# M8330.net
KiCad netlist of a schematic drawn in EAGLE
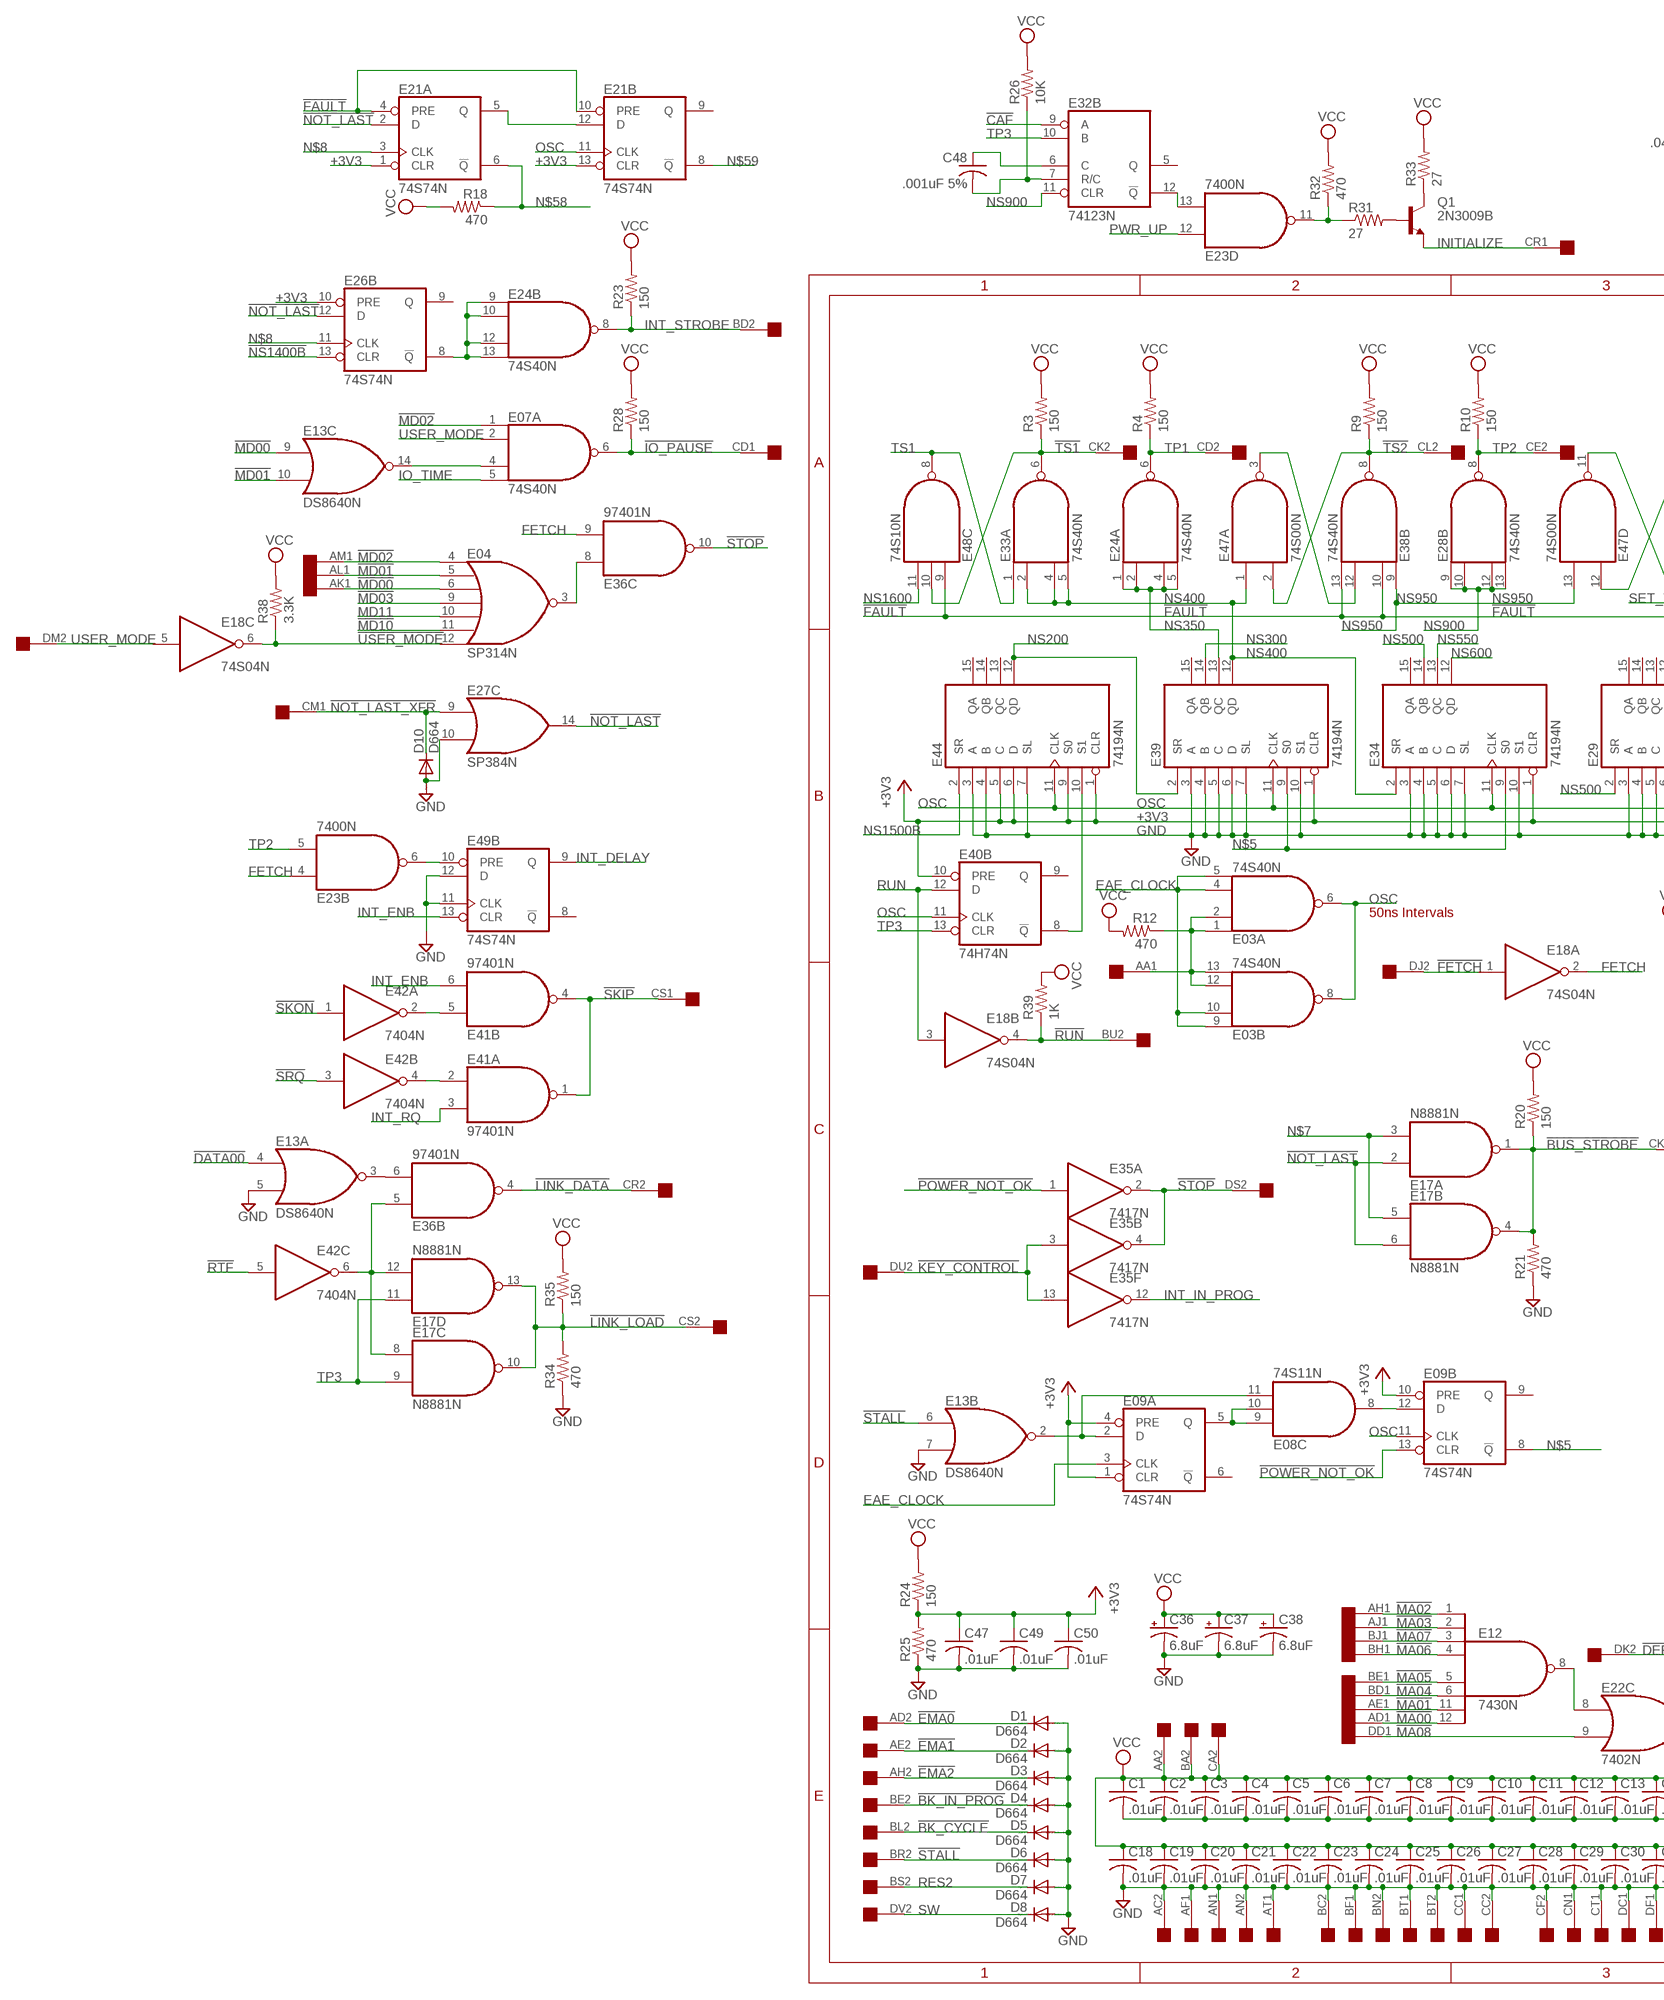
[diagram p0: schematic, sheet 1, part 1 of 2]
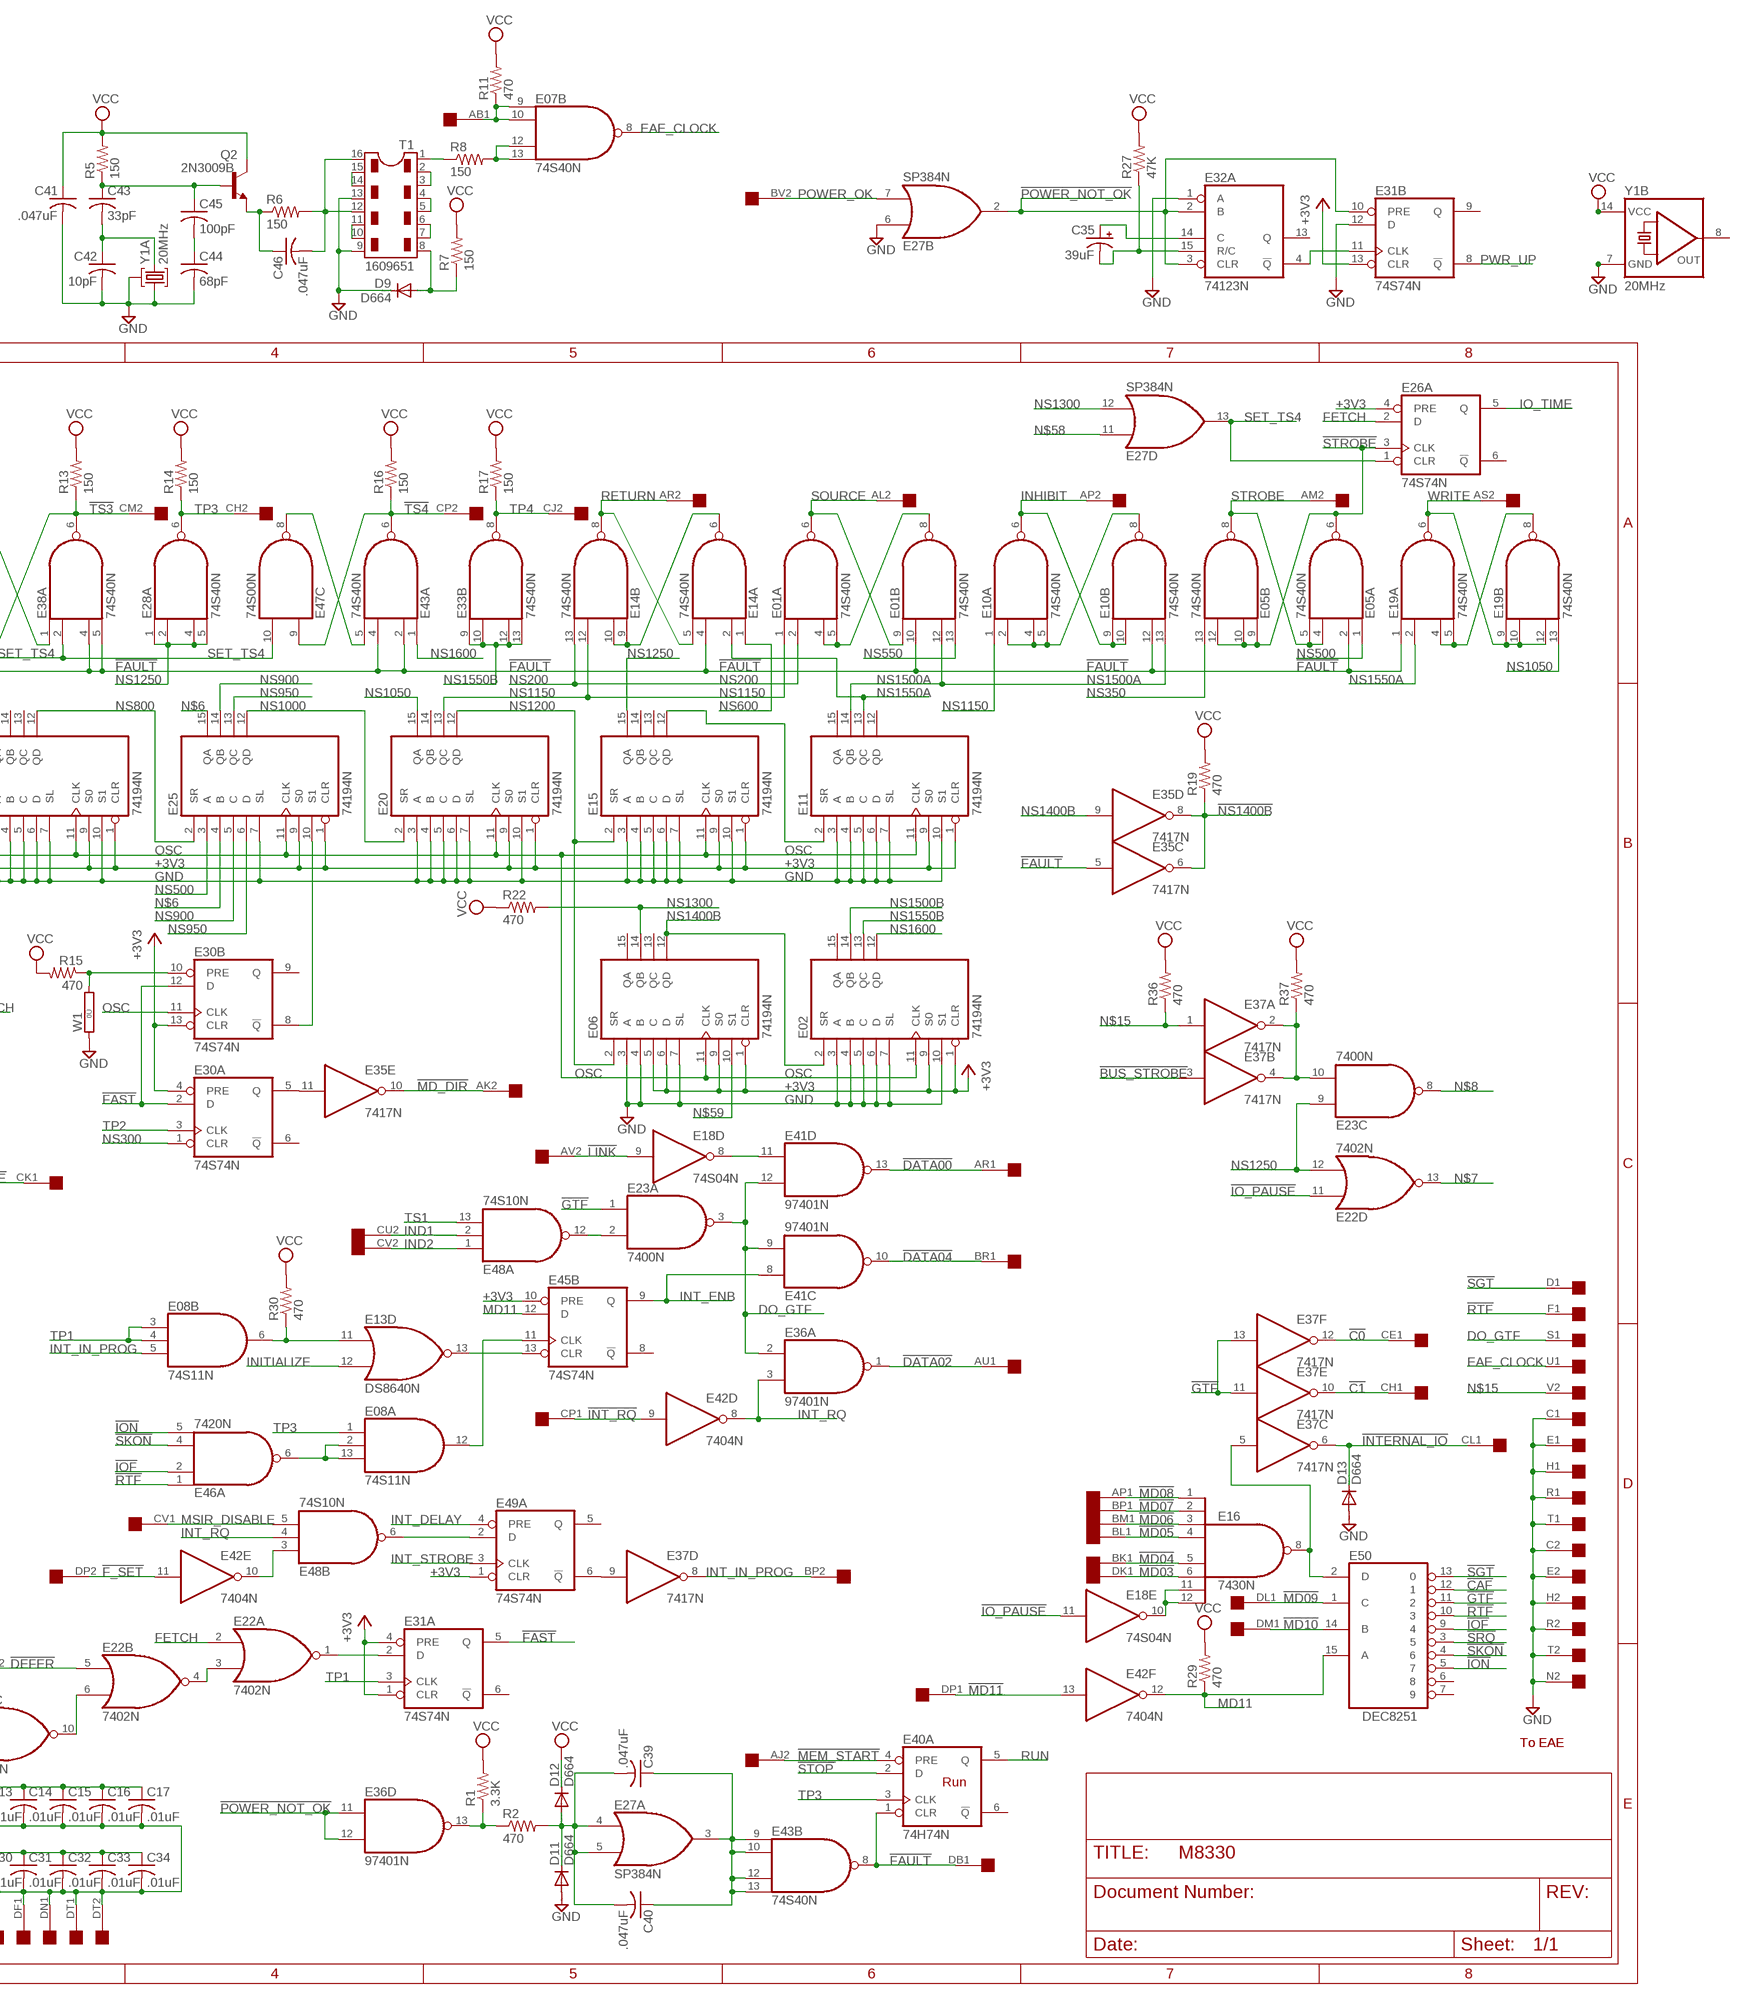
[diagram p1: schematic, sheet 1, part 2 of 2]

(export (version "E")
  (design (tool "Eeschema 10.0.6"))
  (components
    (comp (ref "C1")
      (value ".01uF")
      (footprint "eagle-import:C050-025X075")
      (libsource (lib "eagle-import") (part "C-US050-025X075"))
    )
    (comp (ref "C2")
      (value ".01uF")
      (footprint "eagle-import:C050-025X075")
      (libsource (lib "eagle-import") (part "C-US050-025X075"))
    )
    (comp (ref "C3")
      (value ".01uF")
      (footprint "eagle-import:C050-025X075")
      (libsource (lib "eagle-import") (part "C-US050-025X075"))
    )
    (comp (ref "C4")
      (value ".01uF")
      (footprint "eagle-import:C050-025X075")
      (libsource (lib "eagle-import") (part "C-US050-025X075"))
    )
    (comp (ref "C5")
      (value ".01uF")
      (footprint "eagle-import:C050-025X075")
      (libsource (lib "eagle-import") (part "C-US050-025X075"))
    )
    (comp (ref "C6")
      (value ".01uF")
      (footprint "eagle-import:C050-025X075")
      (libsource (lib "eagle-import") (part "C-US050-025X075"))
    )
    (comp (ref "C7")
      (value ".01uF")
      (footprint "eagle-import:C050-025X075")
      (libsource (lib "eagle-import") (part "C-US050-025X075"))
    )
    (comp (ref "C8")
      (value ".01uF")
      (footprint "eagle-import:C050-025X075")
      (libsource (lib "eagle-import") (part "C-US050-025X075"))
    )
    (comp (ref "C9")
      (value ".01uF")
      (footprint "eagle-import:C050-025X075")
      (libsource (lib "eagle-import") (part "C-US050-025X075"))
    )
    (comp (ref "C10")
      (value ".01uF")
      (footprint "eagle-import:C050-025X075")
      (libsource (lib "eagle-import") (part "C-US050-025X075"))
    )
    (comp (ref "C11")
      (value ".01uF")
      (footprint "eagle-import:C050-025X075")
      (libsource (lib "eagle-import") (part "C-US050-025X075"))
    )
    (comp (ref "C12")
      (value ".01uF")
      (footprint "eagle-import:C050-025X075")
      (libsource (lib "eagle-import") (part "C-US050-025X075"))
    )
    (comp (ref "C13")
      (value ".01uF")
      (footprint "eagle-import:C050-025X075")
      (libsource (lib "eagle-import") (part "C-US050-025X075"))
    )
    (comp (ref "C14")
      (value ".01uF")
      (footprint "eagle-import:C050-025X075")
      (libsource (lib "eagle-import") (part "C-US050-025X075"))
    )
    (comp (ref "C15")
      (value ".01uF")
      (footprint "eagle-import:C050-025X075")
      (libsource (lib "eagle-import") (part "C-US050-025X075"))
    )
    (comp (ref "C16")
      (value ".01uF")
      (footprint "eagle-import:C050-025X075")
      (libsource (lib "eagle-import") (part "C-US050-025X075"))
    )
    (comp (ref "C17")
      (value ".01uF")
      (footprint "eagle-import:C050-025X075")
      (libsource (lib "eagle-import") (part "C-US050-025X075"))
    )
    (comp (ref "C18")
      (value ".01uF")
      (footprint "eagle-import:C050-025X075")
      (libsource (lib "eagle-import") (part "C-US050-025X075"))
    )
    (comp (ref "C19")
      (value ".01uF")
      (footprint "eagle-import:C050-025X075")
      (libsource (lib "eagle-import") (part "C-US050-025X075"))
    )
    (comp (ref "C20")
      (value ".01uF")
      (footprint "eagle-import:C050-025X075")
      (libsource (lib "eagle-import") (part "C-US050-025X075"))
    )
    (comp (ref "C21")
      (value ".01uF")
      (footprint "eagle-import:C050-025X075")
      (libsource (lib "eagle-import") (part "C-US050-025X075"))
    )
    (comp (ref "C22")
      (value ".01uF")
      (footprint "eagle-import:C050-025X075")
      (libsource (lib "eagle-import") (part "C-US050-025X075"))
    )
    (comp (ref "C23")
      (value ".01uF")
      (footprint "eagle-import:C050-025X075")
      (libsource (lib "eagle-import") (part "C-US050-025X075"))
    )
    (comp (ref "C24")
      (value ".01uF")
      (footprint "eagle-import:C050-025X075")
      (libsource (lib "eagle-import") (part "C-US050-025X075"))
    )
    (comp (ref "C25")
      (value ".01uF")
      (footprint "eagle-import:C050-025X075")
      (libsource (lib "eagle-import") (part "C-US050-025X075"))
    )
    (comp (ref "C26")
      (value ".01uF")
      (footprint "eagle-import:C050-025X075")
      (libsource (lib "eagle-import") (part "C-US050-025X075"))
    )
    (comp (ref "C27")
      (value ".01uF")
      (footprint "eagle-import:C050-025X075")
      (libsource (lib "eagle-import") (part "C-US050-025X075"))
    )
    (comp (ref "C28")
      (value ".01uF")
      (footprint "eagle-import:C050-025X075")
      (libsource (lib "eagle-import") (part "C-US050-025X075"))
    )
    (comp (ref "C29")
      (value ".01uF")
      (footprint "eagle-import:C050-025X075")
      (libsource (lib "eagle-import") (part "C-US050-025X075"))
    )
    (comp (ref "C30")
      (value ".01uF")
      (footprint "eagle-import:C050-025X075")
      (libsource (lib "eagle-import") (part "C-US050-025X075"))
    )
    (comp (ref "C31")
      (value ".01uF")
      (footprint "eagle-import:C050-025X075")
      (libsource (lib "eagle-import") (part "C-US050-025X075"))
    )
    (comp (ref "C32")
      (value ".01uF")
      (footprint "eagle-import:C050-025X075")
      (libsource (lib "eagle-import") (part "C-US050-025X075"))
    )
    (comp (ref "C33")
      (value ".01uF")
      (footprint "eagle-import:C050-025X075")
      (libsource (lib "eagle-import") (part "C-US050-025X075"))
    )
    (comp (ref "C34")
      (value ".01uF")
      (footprint "eagle-import:C050-025X075")
      (libsource (lib "eagle-import") (part "C-US050-025X075"))
    )
    (comp (ref "C35")
      (value "39uF")
      (footprint "eagle-import:E12-8")
      (libsource (lib "eagle-import") (part "CPOL-USE20-8AXIAL"))
    )
    (comp (ref "C36")
      (value "6.8uF")
      (footprint "eagle-import:E12-8")
      (libsource (lib "eagle-import") (part "CPOL-USE20-8AXIAL"))
    )
    (comp (ref "C37")
      (value "6.8uF")
      (footprint "eagle-import:E12-8")
      (libsource (lib "eagle-import") (part "CPOL-USE20-8AXIAL"))
    )
    (comp (ref "C38")
      (value "6.8uF")
      (footprint "eagle-import:E12-8")
      (libsource (lib "eagle-import") (part "CPOL-USE20-8AXIAL"))
    )
    (comp (ref "C39")
      (value ".047uF")
      (footprint "eagle-import:C050-025X075")
      (libsource (lib "eagle-import") (part "C-US050-025X075"))
    )
    (comp (ref "C40")
      (value ".047uF")
      (footprint "eagle-import:C050-025X075")
      (libsource (lib "eagle-import") (part "C-US050-025X075"))
    )
    (comp (ref "C41")
      (value ".047uF")
      (footprint "eagle-import:C050-025X075")
      (libsource (lib "eagle-import") (part "C-US050-025X075"))
    )
    (comp (ref "C42")
      (value "10pF")
      (footprint "eagle-import:C050-025X075")
      (libsource (lib "eagle-import") (part "C-US050-025X075"))
    )
    (comp (ref "C43")
      (value "33pF")
      (footprint "eagle-import:C050-025X075")
      (libsource (lib "eagle-import") (part "C-US050-025X075"))
    )
    (comp (ref "C44")
      (value "68pF")
      (footprint "eagle-import:C050-025X075")
      (libsource (lib "eagle-import") (part "C-US050-025X075"))
    )
    (comp (ref "C45")
      (value "100pF")
      (footprint "eagle-import:C050-025X075")
      (libsource (lib "eagle-import") (part "C-US050-025X075"))
    )
    (comp (ref "C46")
      (value ".047uF")
      (footprint "eagle-import:C050-025X075")
      (libsource (lib "eagle-import") (part "C-US050-025X075"))
    )
    (comp (ref "C47")
      (value ".01uF")
      (footprint "eagle-import:C050-025X075")
      (libsource (lib "eagle-import") (part "C-US050-025X075"))
    )
    (comp (ref "C48")
      (value ".001uF 5%")
      (footprint "eagle-import:C050-025X075")
      (libsource (lib "eagle-import") (part "C-US050-025X075"))
    )
    (comp (ref "C49")
      (value ".01uF")
      (footprint "eagle-import:C050-025X075")
      (libsource (lib "eagle-import") (part "C-US050-025X075"))
    )
    (comp (ref "C50")
      (value ".01uF")
      (footprint "eagle-import:C050-025X075")
      (libsource (lib "eagle-import") (part "C-US050-025X075"))
    )
    (comp (ref "D1")
      (value "D664")
      (footprint "eagle-import:DO35-10")
      (libsource (lib "eagle-import") (part "1N4148DO35-10"))
    )
    (comp (ref "D2")
      (value "D664")
      (footprint "eagle-import:DO35-10")
      (libsource (lib "eagle-import") (part "1N4148DO35-10"))
    )
    (comp (ref "D3")
      (value "D664")
      (footprint "eagle-import:DO35-10")
      (libsource (lib "eagle-import") (part "1N4148DO35-10"))
    )
    (comp (ref "D4")
      (value "D664")
      (footprint "eagle-import:DO35-10")
      (libsource (lib "eagle-import") (part "1N4148DO35-10"))
    )
    (comp (ref "D5")
      (value "D664")
      (footprint "eagle-import:DO35-10")
      (libsource (lib "eagle-import") (part "1N4148DO35-10"))
    )
    (comp (ref "D6")
      (value "D664")
      (footprint "eagle-import:DO35-10")
      (libsource (lib "eagle-import") (part "1N4148DO35-10"))
    )
    (comp (ref "D7")
      (value "D664")
      (footprint "eagle-import:DO35-10")
      (libsource (lib "eagle-import") (part "1N4148DO35-10"))
    )
    (comp (ref "D8")
      (value "D664")
      (footprint "eagle-import:DO35-10")
      (libsource (lib "eagle-import") (part "1N4148DO35-10"))
    )
    (comp (ref "D9")
      (value "D664")
      (footprint "eagle-import:DO35-10")
      (libsource (lib "eagle-import") (part "1N4148DO35-10"))
    )
    (comp (ref "D10")
      (value "D664")
      (footprint "eagle-import:DO35-10")
      (libsource (lib "eagle-import") (part "1N4148DO35-10"))
    )
    (comp (ref "D11")
      (value "D664")
      (footprint "eagle-import:DO35-10")
      (libsource (lib "eagle-import") (part "1N4148DO35-10"))
    )
    (comp (ref "D12")
      (value "D664")
      (footprint "eagle-import:DO35-10")
      (libsource (lib "eagle-import") (part "1N4148DO35-10"))
    )
    (comp (ref "D13")
      (value "D664")
      (footprint "eagle-import:DO35-10")
      (libsource (lib "eagle-import") (part "1N4148DO35-10"))
    )
    (comp (ref "E01")
      (value "74S40N")
      (footprint "eagle-import:DIL14")
      (libsource (lib "eagle-import") (part "7420NS"))
    )
    (comp (ref "E02")
      (value "74194N")
      (footprint "eagle-import:DIL16")
      (libsource (lib "eagle-import") (part "74194NS"))
    )
    (comp (ref "E03")
      (value "74S40N")
      (footprint "eagle-import:DIL14")
      (libsource (lib "eagle-import") (part "7420NS"))
    )
    (comp (ref "E04")
      (value "SP314N")
      (footprint "eagle-import:DIL14")
      (libsource (lib "eagle-import") (part "SP314N"))
    )
    (comp (ref "E05")
      (value "74S40N")
      (footprint "eagle-import:DIL14")
      (libsource (lib "eagle-import") (part "7420NS"))
    )
    (comp (ref "E06")
      (value "74194N")
      (footprint "eagle-import:DIL16")
      (libsource (lib "eagle-import") (part "74194NS"))
    )
    (comp (ref "E07")
      (value "74S40N")
      (footprint "eagle-import:DIL14")
      (libsource (lib "eagle-import") (part "7420NS"))
    )
    (comp (ref "E08")
      (value "74S11N")
      (footprint "eagle-import:DIL14")
      (libsource (lib "eagle-import") (part "7411NS"))
    )
    (comp (ref "E09")
      (value "74S74N")
      (footprint "eagle-import:DIL14")
      (libsource (lib "eagle-import") (part "7474NS"))
    )
    (comp (ref "E10")
      (value "74S40N")
      (footprint "eagle-import:DIL14")
      (libsource (lib "eagle-import") (part "7420NS"))
    )
    (comp (ref "E11")
      (value "74194N")
      (footprint "eagle-import:DIL16")
      (libsource (lib "eagle-import") (part "74194NS"))
    )
    (comp (ref "E12")
      (value "7430N")
      (footprint "eagle-import:DIL14")
      (libsource (lib "eagle-import") (part "7430N"))
    )
    (comp (ref "E13")
      (value "DS8640N")
      (footprint "eagle-import:DIL14")
      (libsource (lib "eagle-import") (part "DS8640N"))
    )
    (comp (ref "E14")
      (value "74S40N")
      (footprint "eagle-import:DIL14")
      (libsource (lib "eagle-import") (part "7420NS"))
    )
    (comp (ref "E15")
      (value "74194N")
      (footprint "eagle-import:DIL16")
      (libsource (lib "eagle-import") (part "74194NS"))
    )
    (comp (ref "E16")
      (value "7430N")
      (footprint "eagle-import:DIL14")
      (libsource (lib "eagle-import") (part "7430N"))
    )
    (comp (ref "E17")
      (value "N8881N")
      (footprint "eagle-import:DIL14")
      (libsource (lib "eagle-import") (part "N8881N"))
    )
    (comp (ref "E18")
      (value "74S04N")
      (footprint "eagle-import:DIL14")
      (libsource (lib "eagle-import") (part "7404NS"))
    )
    (comp (ref "E19")
      (value "74S40N")
      (footprint "eagle-import:DIL14")
      (libsource (lib "eagle-import") (part "7420NS"))
    )
    (comp (ref "E20")
      (value "74194N")
      (footprint "eagle-import:DIL16")
      (libsource (lib "eagle-import") (part "74194NS"))
    )
    (comp (ref "E21")
      (value "74S74N")
      (footprint "eagle-import:DIL14")
      (libsource (lib "eagle-import") (part "7474NS"))
    )
    (comp (ref "E22")
      (value "7402N")
      (footprint "eagle-import:DIL14")
      (libsource (lib "eagle-import") (part "7402N"))
    )
    (comp (ref "E23")
      (value "7400N")
      (footprint "eagle-import:DIL14")
      (libsource (lib "eagle-import") (part "7400N"))
    )
    (comp (ref "E24")
      (value "74S40N")
      (footprint "eagle-import:DIL14")
      (libsource (lib "eagle-import") (part "7420NS"))
    )
    (comp (ref "E25")
      (value "74194N")
      (footprint "eagle-import:DIL16")
      (libsource (lib "eagle-import") (part "74194NS"))
    )
    (comp (ref "E26")
      (value "74S74N")
      (footprint "eagle-import:DIL14")
      (libsource (lib "eagle-import") (part "7474NS"))
    )
    (comp (ref "E27")
      (value "SP384N")
      (footprint "eagle-import:DIL14")
      (libsource (lib "eagle-import") (part "SP384N"))
    )
    (comp (ref "E28")
      (value "74S40N")
      (footprint "eagle-import:DIL14")
      (libsource (lib "eagle-import") (part "7420NS"))
    )
    (comp (ref "E29")
      (value "74194N")
      (footprint "eagle-import:DIL16")
      (libsource (lib "eagle-import") (part "74194NS"))
    )
    (comp (ref "E30")
      (value "74S74N")
      (footprint "eagle-import:DIL14")
      (libsource (lib "eagle-import") (part "7474NS"))
    )
    (comp (ref "E31")
      (value "74S74N")
      (footprint "eagle-import:DIL14")
      (libsource (lib "eagle-import") (part "7474NS"))
    )
    (comp (ref "E32")
      (value "74123N")
      (footprint "eagle-import:DIL16")
      (libsource (lib "eagle-import") (part "74123N"))
    )
    (comp (ref "E33")
      (value "74S40N")
      (footprint "eagle-import:DIL14")
      (libsource (lib "eagle-import") (part "7420NS"))
    )
    (comp (ref "E34")
      (value "74194N")
      (footprint "eagle-import:DIL16")
      (libsource (lib "eagle-import") (part "74194NS"))
    )
    (comp (ref "E35")
      (value "7417N")
      (footprint "eagle-import:DIL14")
      (libsource (lib "eagle-import") (part "7417N"))
    )
    (comp (ref "E36")
      (value "97401N")
      (footprint "eagle-import:DIL14")
      (libsource (lib "eagle-import") (part "7401NLS"))
    )
    (comp (ref "E37")
      (value "7417N")
      (footprint "eagle-import:DIL14")
      (libsource (lib "eagle-import") (part "7417N"))
    )
    (comp (ref "E38")
      (value "74S40N")
      (footprint "eagle-import:DIL14")
      (libsource (lib "eagle-import") (part "7420NS"))
    )
    (comp (ref "E39")
      (value "74194N")
      (footprint "eagle-import:DIL16")
      (libsource (lib "eagle-import") (part "74194NS"))
    )
    (comp (ref "E40")
      (value "74H74N")
      (footprint "eagle-import:DIL14")
      (libsource (lib "eagle-import") (part "7474NS"))
    )
    (comp (ref "E41")
      (value "97401N")
      (footprint "eagle-import:DIL14")
      (libsource (lib "eagle-import") (part "7401NLS"))
    )
    (comp (ref "E42")
      (value "7404N")
      (footprint "eagle-import:DIL14")
      (libsource (lib "eagle-import") (part "7404N"))
    )
    (comp (ref "E43")
      (value "74S40N")
      (footprint "eagle-import:DIL14")
      (libsource (lib "eagle-import") (part "7420NS"))
    )
    (comp (ref "E44")
      (value "74194N")
      (footprint "eagle-import:DIL16")
      (libsource (lib "eagle-import") (part "74194NS"))
    )
    (comp (ref "E45")
      (value "74S74N")
      (footprint "eagle-import:DIL14")
      (libsource (lib "eagle-import") (part "7474NS"))
    )
    (comp (ref "E46")
      (value "7420N")
      (footprint "eagle-import:DIL14")
      (libsource (lib "eagle-import") (part "7420NLS"))
    )
    (comp (ref "E47")
      (value "74S00N")
      (footprint "eagle-import:DIL14")
      (libsource (lib "eagle-import") (part "7400NS"))
    )
    (comp (ref "E48")
      (value "74S10N")
      (footprint "eagle-import:DIL14")
      (libsource (lib "eagle-import") (part "7410NS"))
    )
    (comp (ref "E49")
      (value "74S74N")
      (footprint "eagle-import:DIL14")
      (libsource (lib "eagle-import") (part "7474NS"))
    )
    (comp (ref "E50")
      (value "DEC8251")
      (footprint "eagle-import:DIL16")
      (libsource (lib "eagle-import") (part "DEC8251"))
    )
    (comp (ref "J")
      (value "SINGLE")
      (footprint "eagle-import:EDGE-CON2")
      (libsource (lib "eagle-import") (part "SINGLE"))
    )
    (comp (ref "Q1")
      (value "2N3009B")
      (footprint "eagle-import:TO5")
      (libsource (lib "eagle-import") (part "-NPN-TO5"))
    )
    (comp (ref "Q2")
      (value "2N3009B")
      (footprint "eagle-import:TO5")
      (libsource (lib "eagle-import") (part "-NPN-TO5"))
    )
    (comp (ref "R1")
      (value "3.3K")
      (footprint "eagle-import:0207_10")
      (libsource (lib "eagle-import") (part "R-US_0207/10"))
    )
    (comp (ref "R2")
      (value "470")
      (footprint "eagle-import:0207_10")
      (libsource (lib "eagle-import") (part "R-US_0207/10"))
    )
    (comp (ref "R3")
      (value "150")
      (footprint "eagle-import:0207_10")
      (libsource (lib "eagle-import") (part "R-US_0207/10"))
    )
    (comp (ref "R4")
      (value "150")
      (footprint "eagle-import:0207_10")
      (libsource (lib "eagle-import") (part "R-US_0207/10"))
    )
    (comp (ref "R5")
      (value "150")
      (footprint "eagle-import:0207_10")
      (libsource (lib "eagle-import") (part "R-US_0207/10"))
    )
    (comp (ref "R6")
      (value "150")
      (footprint "eagle-import:0207_10")
      (libsource (lib "eagle-import") (part "R-US_0207/10"))
    )
    (comp (ref "R7")
      (value "150")
      (footprint "eagle-import:0207_10")
      (libsource (lib "eagle-import") (part "R-US_0207/10"))
    )
    (comp (ref "R8")
      (value "150")
      (footprint "eagle-import:0207_10")
      (libsource (lib "eagle-import") (part "R-US_0207/10"))
    )
    (comp (ref "R9")
      (value "150")
      (footprint "eagle-import:0207_10")
      (libsource (lib "eagle-import") (part "R-US_0207/10"))
    )
    (comp (ref "R10")
      (value "150")
      (footprint "eagle-import:0207_10")
      (libsource (lib "eagle-import") (part "R-US_0207/10"))
    )
    (comp (ref "R11")
      (value "470")
      (footprint "eagle-import:0207_10")
      (libsource (lib "eagle-import") (part "R-US_0207/10"))
    )
    (comp (ref "R12")
      (value "470")
      (footprint "eagle-import:0207_10")
      (libsource (lib "eagle-import") (part "R-US_0207/10"))
    )
    (comp (ref "R13")
      (value "150")
      (footprint "eagle-import:0207_10")
      (libsource (lib "eagle-import") (part "R-US_0207/10"))
    )
    (comp (ref "R14")
      (value "150")
      (footprint "eagle-import:0207_10")
      (libsource (lib "eagle-import") (part "R-US_0207/10"))
    )
    (comp (ref "R15")
      (value "470")
      (footprint "eagle-import:0207_10")
      (libsource (lib "eagle-import") (part "R-US_0207/10"))
    )
    (comp (ref "R16")
      (value "150")
      (footprint "eagle-import:0207_10")
      (libsource (lib "eagle-import") (part "R-US_0207/10"))
    )
    (comp (ref "R17")
      (value "150")
      (footprint "eagle-import:0207_10")
      (libsource (lib "eagle-import") (part "R-US_0207/10"))
    )
    (comp (ref "R18")
      (value "470")
      (footprint "eagle-import:0207_10")
      (libsource (lib "eagle-import") (part "R-US_0207/10"))
    )
    (comp (ref "R19")
      (value "470")
      (footprint "eagle-import:0207_10")
      (libsource (lib "eagle-import") (part "R-US_0207/10"))
    )
    (comp (ref "R20")
      (value "150")
      (footprint "eagle-import:0207_10")
      (libsource (lib "eagle-import") (part "R-US_0207/10"))
    )
    (comp (ref "R21")
      (value "470")
      (footprint "eagle-import:0207_10")
      (libsource (lib "eagle-import") (part "R-US_0207/10"))
    )
    (comp (ref "R22")
      (value "470")
      (footprint "eagle-import:0207_10")
      (libsource (lib "eagle-import") (part "R-US_0207/10"))
    )
    (comp (ref "R23")
      (value "150")
      (footprint "eagle-import:0207_10")
      (libsource (lib "eagle-import") (part "R-US_0207/10"))
    )
    (comp (ref "R24")
      (value "150")
      (footprint "eagle-import:0207_10")
      (libsource (lib "eagle-import") (part "R-US_0207/10"))
    )
    (comp (ref "R25")
      (value "470")
      (footprint "eagle-import:0207_10")
      (libsource (lib "eagle-import") (part "R-US_0207/10"))
    )
    (comp (ref "R26")
      (value "10K")
      (footprint "eagle-import:0207_10")
      (libsource (lib "eagle-import") (part "R-US_0207/10"))
    )
    (comp (ref "R27")
      (value "47K")
      (footprint "eagle-import:0207_10")
      (libsource (lib "eagle-import") (part "R-US_0207/10"))
    )
    (comp (ref "R28")
      (value "150")
      (footprint "eagle-import:0207_10")
      (libsource (lib "eagle-import") (part "R-US_0207/10"))
    )
    (comp (ref "R29")
      (value "470")
      (footprint "eagle-import:0207_10")
      (libsource (lib "eagle-import") (part "R-US_0207/10"))
    )
    (comp (ref "R30")
      (value "470")
      (footprint "eagle-import:0207_10")
      (libsource (lib "eagle-import") (part "R-US_0207/10"))
    )
    (comp (ref "R31")
      (value "27")
      (footprint "eagle-import:0207_10")
      (libsource (lib "eagle-import") (part "R-US_0207/10"))
    )
    (comp (ref "R32")
      (value "470")
      (footprint "eagle-import:0207_10")
      (libsource (lib "eagle-import") (part "R-US_0207/10"))
    )
    (comp (ref "R33")
      (value "27")
      (footprint "eagle-import:0207_10")
      (libsource (lib "eagle-import") (part "R-US_0207/10"))
    )
    (comp (ref "R34")
      (value "470")
      (footprint "eagle-import:0207_10")
      (libsource (lib "eagle-import") (part "R-US_0207/10"))
    )
    (comp (ref "R35")
      (value "150")
      (footprint "eagle-import:0207_10")
      (libsource (lib "eagle-import") (part "R-US_0207/10"))
    )
    (comp (ref "R36")
      (value "470")
      (footprint "eagle-import:0207_10")
      (libsource (lib "eagle-import") (part "R-US_0207/10"))
    )
    (comp (ref "R37")
      (value "470")
      (footprint "eagle-import:0207_10")
      (libsource (lib "eagle-import") (part "R-US_0207/10"))
    )
    (comp (ref "R38")
      (value "3.3K")
      (footprint "eagle-import:0207_10")
      (libsource (lib "eagle-import") (part "R-US_0207/10"))
    )
    (comp (ref "R39")
      (value "1K")
      (footprint "eagle-import:0207_10")
      (libsource (lib "eagle-import") (part "R-US_0207/10"))
    )
    (comp (ref "T1")
      (value "1609651")
      (footprint "eagle-import:DIL16")
      (libsource (lib "eagle-import") (part "DIL16"))
    )
    (comp (ref "U$2")
      (value "QUAD")
      (footprint "eagle-import:EDGE-CON8")
      (libsource (lib "eagle-import") (part "QUAD"))
    )
    (comp (ref "W1")
      (value "0R")
      (footprint "eagle-import:0R_10")
      (libsource (lib "eagle-import") (part "0R"))
    )
    (comp (ref "Y1A")
      (value "20MHz")
      (footprint "eagle-import:HC49TL-H")
      (libsource (lib "eagle-import") (part "HC49TL-H"))
    )
    (comp (ref "Y1B")
      (value "20MHz")
      (footprint "eagle-import:DIL14S")
      (libsource (lib "eagle-import") (part "QG5860"))
    )
  )
  (nets
    (net (code "1") (name "+3V3") (class "Default")
      (node (ref "C47") (pin "1") (pinfunction "1_1") (pintype "passive"))
      (node (ref "C49") (pin "1") (pinfunction "1_1") (pintype "passive"))
      (node (ref "C50") (pin "1") (pinfunction "1_1") (pintype "passive"))
      (node (ref "E02") (pin "1") (pinfunction "CLR_1") (pintype "input"))
      (node (ref "E02") (pin "9") (pinfunction "S0_9") (pintype "input"))
      (node (ref "E06") (pin "1") (pinfunction "CLR_1") (pintype "input"))
      (node (ref "E06") (pin "5") (pinfunction "C_5") (pintype "input"))
      (node (ref "E06") (pin "6") (pinfunction "D_6") (pintype "input"))
      (node (ref "E06") (pin "9") (pinfunction "S0_9") (pintype "input"))
      (node (ref "E09") (pin "1") (pinfunction "CLR_1") (pintype "input"))
      (node (ref "E09") (pin "10") (pinfunction "PRE_10") (pintype "input"))
      (node (ref "E09") (pin "4") (pinfunction "PRE_4") (pintype "input"))
      (node (ref "E11") (pin "1") (pinfunction "CLR_1") (pintype "input"))
      (node (ref "E11") (pin "9") (pinfunction "S0_9") (pintype "input"))
      (node (ref "E15") (pin "1") (pinfunction "CLR_1") (pintype "input"))
      (node (ref "E15") (pin "9") (pinfunction "S0_9") (pintype "input"))
      (node (ref "E20") (pin "1") (pinfunction "CLR_1") (pintype "input"))
      (node (ref "E20") (pin "9") (pinfunction "S0_9") (pintype "input"))
      (node (ref "E21") (pin "1") (pinfunction "CLR_1") (pintype "input"))
      (node (ref "E21") (pin "13") (pinfunction "CLR_13") (pintype "input"))
      (node (ref "E25") (pin "1") (pinfunction "CLR_1") (pintype "input"))
      (node (ref "E25") (pin "9") (pinfunction "S0_9") (pintype "input"))
      (node (ref "E26") (pin "10") (pinfunction "PRE_10") (pintype "input"))
      (node (ref "E26") (pin "4") (pinfunction "PRE_4") (pintype "input"))
      (node (ref "E29") (pin "1") (pinfunction "CLR_1") (pintype "input"))
      (node (ref "E29") (pin "9") (pinfunction "S0_9") (pintype "input"))
      (node (ref "E30") (pin "13") (pinfunction "CLR_13") (pintype "input"))
      (node (ref "E30") (pin "4") (pinfunction "PRE_4") (pintype "input"))
      (node (ref "E31") (pin "1") (pinfunction "CLR_1") (pintype "input"))
      (node (ref "E31") (pin "13") (pinfunction "CLR_13") (pintype "input"))
      (node (ref "E31") (pin "4") (pinfunction "PRE_4") (pintype "input"))
      (node (ref "E34") (pin "1") (pinfunction "CLR_1") (pintype "input"))
      (node (ref "E39") (pin "1") (pinfunction "CLR_1") (pintype "input"))
      (node (ref "E40") (pin "10") (pinfunction "PRE_10") (pintype "input"))
      (node (ref "E44") (pin "1") (pinfunction "CLR_1") (pintype "input"))
      (node (ref "E44") (pin "5") (pinfunction "C_5") (pintype "input"))
      (node (ref "E44") (pin "6") (pinfunction "D_6") (pintype "input"))
      (node (ref "E44") (pin "9") (pinfunction "S0_9") (pintype "input"))
      (node (ref "E45") (pin "10") (pinfunction "PRE_10") (pintype "input"))
      (node (ref "E49") (pin "1") (pinfunction "CLR_1") (pintype "input"))
      (node (ref "R24") (pin "1") (pinfunction "1_1") (pintype "passive"))
      (node (ref "R25") (pin "2") (pinfunction "2_2") (pintype "passive"))
    )
    (net (code "2") (name "/DO_GTF") (class "Default")
      (node (ref "E23") (pin "3") (pinfunction "O_3") (pintype "output"))
      (node (ref "E36") (pin "2") (pinfunction "I0_2") (pintype "input"))
      (node (ref "E41") (pin "12") (pinfunction "I1_12") (pintype "input"))
      (node (ref "E41") (pin "9") (pinfunction "I1_9") (pintype "input"))
      (node (ref "J") (pin "S1") (pinfunction "1_S1") (pintype "bidirectional"))
    )
    (net (code "3") (name "/EAE_CLOCK") (class "Default")
      (node (ref "E03") (pin "10") (pinfunction "I1_10") (pintype "input"))
      (node (ref "E03") (pin "4") (pinfunction "I2_4") (pintype "input"))
      (node (ref "E03") (pin "5") (pinfunction "I3_5") (pintype "input"))
      (node (ref "E03") (pin "9") (pinfunction "I0_9") (pintype "input"))
      (node (ref "E07") (pin "8") (pinfunction "O_8") (pintype "output"))
      (node (ref "E09") (pin "3") (pinfunction "CLK_3") (pintype "input"))
      (node (ref "J") (pin "U1") (pinfunction "1_U1") (pintype "bidirectional"))
    )
    (net (code "4") (name "/FETCH") (class "Default")
      (node (ref "E18") (pin "2") (pinfunction "O_2") (pintype "output"))
      (node (ref "E22") (pin "2") (pinfunction "I0_2") (pintype "input"))
      (node (ref "E23") (pin "4") (pinfunction "I0_4") (pintype "input"))
      (node (ref "E26") (pin "2") (pinfunction "D_2") (pintype "input"))
      (node (ref "E36") (pin "9") (pinfunction "I1_9") (pintype "input"))
    )
    (net (code "5") (name "/IND1") (class "Default")
      (node (ref "E48") (pin "2") (pinfunction "I1_2") (pintype "input"))
      (node (ref "U$2") (pin "CU2") (pinfunction "1_CU2") (pintype "bidirectional"))
    )
    (net (code "6") (name "/IND2") (class "Default")
      (node (ref "E48") (pin "1") (pinfunction "I0_1") (pintype "input"))
      (node (ref "U$2") (pin "CV2") (pinfunction "1_CV2") (pintype "bidirectional"))
    )
    (net (code "7") (name "/INHIBIT") (class "Default")
      (node (ref "E10") (pin "10") (pinfunction "I1_10") (pintype "input"))
      (node (ref "E10") (pin "6") (pinfunction "O_6") (pintype "output"))
      (node (ref "E10") (pin "9") (pinfunction "I0_9") (pintype "input"))
      (node (ref "U$2") (pin "AP2") (pinfunction "1_AP2") (pintype "bidirectional"))
    )
    (net (code "8") (name "/INITIALIZE") (class "Default")
      (node (ref "E13") (pin "12") (pinfunction "I1_12") (pintype "input"))
      (node (ref "Q1") (pin "1") (pinfunction "E_1") (pintype "passive"))
      (node (ref "U$2") (pin "CR1") (pinfunction "1_CR1") (pintype "bidirectional"))
    )
    (net (code "9") (name "/INT_DELAY") (class "Default")
      (node (ref "E49") (pin "4") (pinfunction "PRE_4") (pintype "input"))
      (node (ref "E49") (pin "9") (pinfunction "Q_9") (pintype "output"))
    )
    (net (code "10") (name "/INT_ENB") (class "Default")
      (node (ref "E41") (pin "6") (pinfunction "I1_6") (pintype "input"))
      (node (ref "E41") (pin "8") (pinfunction "I0_8") (pintype "input"))
      (node (ref "E45") (pin "9") (pinfunction "Q_9") (pintype "output"))
      (node (ref "E49") (pin "13") (pinfunction "CLR_13") (pintype "input"))
    )
    (net (code "11") (name "/INT_IN_PROG") (class "Default")
      (node (ref "E08") (pin "5") (pinfunction "I2_5") (pintype "input"))
      (node (ref "E35") (pin "12") (pinfunction "O_12") (pintype "open_collector"))
      (node (ref "E37") (pin "8") (pinfunction "O_8") (pintype "open_collector"))
      (node (ref "U$2") (pin "BP2") (pinfunction "1_BP2") (pintype "bidirectional"))
    )
    (net (code "12") (name "/INT_RQ") (class "Default")
      (node (ref "E36") (pin "3") (pinfunction "I1_3") (pintype "input"))
      (node (ref "E41") (pin "3") (pinfunction "I1_3") (pintype "input"))
      (node (ref "E42") (pin "8") (pinfunction "O_8") (pintype "output"))
      (node (ref "E48") (pin "4") (pinfunction "I1_4") (pintype "input"))
    )
    (net (code "13") (name "/INT_STROBE") (class "Default")
      (node (ref "E24") (pin "8") (pinfunction "O_8") (pintype "output"))
      (node (ref "E49") (pin "3") (pinfunction "CLK_3") (pintype "input"))
      (node (ref "R23") (pin "1") (pinfunction "1_1") (pintype "passive"))
      (node (ref "U$2") (pin "BD2") (pinfunction "1_BD2") (pintype "bidirectional"))
    )
    (net (code "14") (name "/IO_TIME") (class "Default")
      (node (ref "E07") (pin "5") (pinfunction "I3_5") (pintype "input"))
      (node (ref "E26") (pin "5") (pinfunction "Q_5") (pintype "output"))
    )
    (net (code "15") (name "/MD11") (class "Default")
      (node (ref "E04") (pin "10") (pinfunction "I4_10") (pintype "input"))
      (node (ref "E42") (pin "12") (pinfunction "O_12") (pintype "output"))
      (node (ref "E45") (pin "12") (pinfunction "D_12") (pintype "input"))
      (node (ref "E50") (pin "15") (pinfunction "A_15") (pintype "input"))
      (node (ref "R29") (pin "1") (pinfunction "1_1") (pintype "passive"))
    )
    (net (code "16") (name "/MSIR_DISABLE") (class "Default")
      (node (ref "E48") (pin "5") (pinfunction "I2_5") (pintype "input"))
      (node (ref "U$2") (pin "CV1") (pinfunction "1_CV1") (pintype "bidirectional"))
    )
    (net (code "17") (name "/N$5") (class "Default")
      (node (ref "E09") (pin "8") (pinfunction "~{Q}_8") (pintype "output"))
      (node (ref "E34") (pin "9") (pinfunction "S0_9") (pintype "input"))
      (node (ref "E39") (pin "9") (pinfunction "S0_9") (pintype "input"))
    )
    (net (code "18") (name "/N$6") (class "Default")
      (node (ref "E25") (pin "15") (pinfunction "QA_15") (pintype "output"))
      (node (ref "E25") (pin "4") (pinfunction "B_4") (pintype "input"))
    )
    (net (code "19") (name "/N$7") (class "Default")
      (node (ref "E17") (pin "3") (pinfunction "I1_3") (pintype "input"))
      (node (ref "E17") (pin "5") (pinfunction "I0_5") (pintype "input"))
      (node (ref "E22") (pin "13") (pinfunction "O_13") (pintype "output"))
    )
    (net (code "20") (name "/N$8") (class "Default")
      (node (ref "E21") (pin "3") (pinfunction "CLK_3") (pintype "input"))
      (node (ref "E23") (pin "8") (pinfunction "O_8") (pintype "output"))
      (node (ref "E26") (pin "11") (pinfunction "CLK_11") (pintype "input"))
    )
    (net (code "21") (name "/N$15") (class "Default")
      (node (ref "E37") (pin "1") (pinfunction "I_1") (pintype "input"))
      (node (ref "J") (pin "V2") (pinfunction "1_V2") (pintype "bidirectional"))
      (node (ref "R36") (pin "1") (pinfunction "1_1") (pintype "passive"))
    )
    (net (code "22") (name "/N$58") (class "Default")
      (node (ref "E21") (pin "6") (pinfunction "~{Q}_6") (pintype "output"))
      (node (ref "E27") (pin "11") (pinfunction "I0_11") (pintype "input"))
      (node (ref "R18") (pin "1") (pinfunction "1_1") (pintype "passive"))
    )
    (net (code "23") (name "/N$59") (class "Default")
      (node (ref "E06") (pin "10") (pinfunction "S1_10") (pintype "input"))
      (node (ref "E21") (pin "8") (pinfunction "~{Q}_8") (pintype "output"))
    )
    (net (code "24") (name "/NS200") (class "Default")
      (node (ref "E01") (pin "2") (pinfunction "I1_2") (pintype "input"))
      (node (ref "E14") (pin "13") (pinfunction "I3_13") (pintype "input"))
      (node (ref "E39") (pin "2") (pinfunction "SR_2") (pintype "input"))
      (node (ref "E44") (pin "12") (pinfunction "QD_12") (pintype "output"))
    )
    (net (code "25") (name "/NS300") (class "Default")
      (node (ref "E30") (pin "1") (pinfunction "CLR_1") (pintype "input"))
      (node (ref "E39") (pin "14") (pinfunction "QB_14") (pintype "output"))
    )
    (net (code "26") (name "/NS350") (class "Default")
      (node (ref "E05") (pin "13") (pinfunction "I3_13") (pintype "input"))
      (node (ref "E24") (pin "1") (pinfunction "I0_1") (pintype "input"))
      (node (ref "E24") (pin "2") (pinfunction "I1_2") (pintype "input"))
      (node (ref "E24") (pin "4") (pinfunction "I2_4") (pintype "input"))
      (node (ref "E24") (pin "5") (pinfunction "I3_5") (pintype "input"))
      (node (ref "E39") (pin "13") (pinfunction "QC_13") (pintype "output"))
    )
    (net (code "27") (name "/NS400") (class "Default")
      (node (ref "E33") (pin "2") (pinfunction "I1_2") (pintype "input"))
      (node (ref "E33") (pin "4") (pinfunction "I2_4") (pintype "input"))
      (node (ref "E33") (pin "5") (pinfunction "I3_5") (pintype "input"))
      (node (ref "E34") (pin "2") (pinfunction "SR_2") (pintype "input"))
      (node (ref "E39") (pin "12") (pinfunction "QD_12") (pintype "output"))
      (node (ref "E47") (pin "1") (pinfunction "I0_1") (pintype "input"))
    )
    (net (code "28") (name "/NS500") (class "Default")
      (node (ref "E05") (pin "1") (pinfunction "I0_1") (pintype "input"))
      (node (ref "E25") (pin "3") (pinfunction "A_3") (pintype "input"))
      (node (ref "E29") (pin "2") (pinfunction "SR_2") (pintype "input"))
      (node (ref "E34") (pin "14") (pinfunction "QB_14") (pintype "output"))
    )
    (net (code "29") (name "/NS550") (class "Default")
      (node (ref "E01") (pin "13") (pinfunction "I3_13") (pintype "input"))
      (node (ref "E34") (pin "13") (pinfunction "QC_13") (pintype "output"))
    )
    (net (code "30") (name "/NS600") (class "Default")
      (node (ref "E14") (pin "1") (pinfunction "I0_1") (pintype "input"))
      (node (ref "E34") (pin "12") (pinfunction "QD_12") (pintype "output"))
    )
    (net (code "31") (name "/NS800") (class "Default")
      (node (ref "E25") (pin "2") (pinfunction "SR_2") (pintype "input"))
      (node (ref "E29") (pin "12") (pinfunction "QD_12") (pintype "output"))
    )
    (net (code "32") (name "/NS900") (class "Default")
      (node (ref "E25") (pin "14") (pinfunction "QB_14") (pintype "output"))
      (node (ref "E25") (pin "5") (pinfunction "C_5") (pintype "input"))
      (node (ref "E28") (pin "10") (pinfunction "I1_10") (pintype "input"))
      (node (ref "E28") (pin "12") (pinfunction "I2_12") (pintype "input"))
      (node (ref "E28") (pin "13") (pinfunction "I3_13") (pintype "input"))
      (node (ref "E28") (pin "9") (pinfunction "I0_9") (pintype "input"))
      (node (ref "E32") (pin "11") (pinfunction "CLR_11") (pintype "input"))
    )
    (net (code "33") (name "/NS950") (class "Default")
      (node (ref "E25") (pin "13") (pinfunction "QC_13") (pintype "output"))
      (node (ref "E25") (pin "6") (pinfunction "D_6") (pintype "input"))
      (node (ref "E38") (pin "9") (pinfunction "I0_9") (pintype "input"))
      (node (ref "E47") (pin "13") (pinfunction "I1_13") (pintype "input"))
    )
    (net (code "34") (name "/NS1000") (class "Default")
      (node (ref "E20") (pin "2") (pinfunction "SR_2") (pintype "input"))
      (node (ref "E25") (pin "12") (pinfunction "QD_12") (pintype "output"))
    )
    (net (code "35") (name "/NS1050") (class "Default")
      (node (ref "E19") (pin "13") (pinfunction "I3_13") (pintype "input"))
      (node (ref "E20") (pin "15") (pinfunction "QA_15") (pintype "output"))
    )
    (net (code "36") (name "/NS1150") (class "Default")
      (node (ref "E01") (pin "1") (pinfunction "I0_1") (pintype "input"))
      (node (ref "E10") (pin "1") (pinfunction "I0_1") (pintype "input"))
      (node (ref "E14") (pin "12") (pinfunction "I2_12") (pintype "input"))
      (node (ref "E20") (pin "13") (pinfunction "QC_13") (pintype "output"))
    )
    (net (code "37") (name "/NS1200") (class "Default")
      (node (ref "E06") (pin "2") (pinfunction "SR_2") (pintype "input"))
      (node (ref "E15") (pin "2") (pinfunction "SR_2") (pintype "input"))
      (node (ref "E20") (pin "12") (pinfunction "QD_12") (pintype "output"))
    )
    (net (code "38") (name "/NS1250") (class "Default")
      (node (ref "E15") (pin "15") (pinfunction "QA_15") (pintype "output"))
      (node (ref "E22") (pin "12") (pinfunction "I1_12") (pintype "input"))
      (node (ref "E23") (pin "9") (pinfunction "I0_9") (pintype "input"))
      (node (ref "E28") (pin "1") (pinfunction "I0_1") (pintype "input"))
      (node (ref "E28") (pin "2") (pinfunction "I1_2") (pintype "input"))
      (node (ref "E28") (pin "4") (pinfunction "I2_4") (pintype "input"))
      (node (ref "E28") (pin "5") (pinfunction "I3_5") (pintype "input"))
    )
    (net (code "39") (name "/NS1300") (class "Default")
      (node (ref "E06") (pin "14") (pinfunction "QB_14") (pintype "output"))
      (node (ref "E27") (pin "12") (pinfunction "I1_12") (pintype "input"))
      (node (ref "R22") (pin "2") (pinfunction "2_2") (pintype "passive"))
    )
    (net (code "40") (name "/NS1400B") (class "Default")
      (node (ref "E02") (pin "2") (pinfunction "SR_2") (pintype "input"))
      (node (ref "E06") (pin "12") (pinfunction "QD_12") (pintype "output"))
      (node (ref "E35") (pin "9") (pinfunction "I_9") (pintype "input"))
    )
    (net (code "41") (name "/NS1500A") (class "Default")
      (node (ref "E01") (pin "12") (pinfunction "I2_12") (pintype "input"))
      (node (ref "E10") (pin "13") (pinfunction "I3_13") (pintype "input"))
      (node (ref "E11") (pin "14") (pinfunction "QB_14") (pintype "output"))
    )
    (net (code "42") (name "/NS1500B") (class "Default")
      (node (ref "E02") (pin "14") (pinfunction "QB_14") (pintype "output"))
      (node (ref "E44") (pin "2") (pinfunction "SR_2") (pintype "input"))
    )
    (net (code "43") (name "/NS1550A") (class "Default")
      (node (ref "E11") (pin "13") (pinfunction "QC_13") (pintype "output"))
      (node (ref "E14") (pin "2") (pinfunction "I1_2") (pintype "input"))
      (node (ref "E19") (pin "2") (pinfunction "I1_2") (pintype "input"))
    )
    (net (code "44") (name "/NS1550B") (class "Default")
      (node (ref "E02") (pin "13") (pinfunction "QC_13") (pintype "output"))
      (node (ref "E33") (pin "10") (pinfunction "I1_10") (pintype "input"))
      (node (ref "E33") (pin "12") (pinfunction "I2_12") (pintype "input"))
      (node (ref "E33") (pin "13") (pinfunction "I3_13") (pintype "input"))
      (node (ref "E33") (pin "9") (pinfunction "I0_9") (pintype "input"))
    )
    (net (code "45") (name "/NS1600") (class "Default")
      (node (ref "E02") (pin "12") (pinfunction "QD_12") (pintype "output"))
      (node (ref "E43") (pin "1") (pinfunction "I0_1") (pintype "input"))
      (node (ref "E48") (pin "11") (pinfunction "I2_11") (pintype "input"))
    )
    (net (code "46") (name "/OSC") (class "Default")
      (node (ref "E02") (pin "11") (pinfunction "CLK_11") (pintype "input"))
      (node (ref "E03") (pin "6") (pinfunction "O_6") (pintype "output"))
      (node (ref "E03") (pin "8") (pinfunction "O_8") (pintype "output"))
      (node (ref "E06") (pin "11") (pinfunction "CLK_11") (pintype "input"))
      (node (ref "E09") (pin "11") (pinfunction "CLK_11") (pintype "input"))
      (node (ref "E11") (pin "11") (pinfunction "CLK_11") (pintype "input"))
      (node (ref "E15") (pin "11") (pinfunction "CLK_11") (pintype "input"))
      (node (ref "E20") (pin "11") (pinfunction "CLK_11") (pintype "input"))
      (node (ref "E21") (pin "11") (pinfunction "CLK_11") (pintype "input"))
      (node (ref "E25") (pin "11") (pinfunction "CLK_11") (pintype "input"))
      (node (ref "E29") (pin "11") (pinfunction "CLK_11") (pintype "input"))
      (node (ref "E30") (pin "11") (pinfunction "CLK_11") (pintype "input"))
      (node (ref "E34") (pin "11") (pinfunction "CLK_11") (pintype "input"))
      (node (ref "E39") (pin "11") (pinfunction "CLK_11") (pintype "input"))
      (node (ref "E40") (pin "11") (pinfunction "CLK_11") (pintype "input"))
      (node (ref "E44") (pin "11") (pinfunction "CLK_11") (pintype "input"))
    )
    (net (code "47") (name "/POWER_OK") (class "Default")
      (node (ref "E27") (pin "7") (pinfunction "I1_7") (pintype "input"))
      (node (ref "U$2") (pin "BV2") (pinfunction "1_BV2") (pintype "bidirectional"))
    )
    (net (code "48") (name "/PWR_UP") (class "Default")
      (node (ref "E23") (pin "12") (pinfunction "I0_12") (pintype "input"))
      (node (ref "E31") (pin "8") (pinfunction "~{Q}_8") (pintype "output"))
    )
    (net (code "49") (name "/RES2") (class "Default")
      (node (ref "D7") (pin "C") (pinfunction "C_C") (pintype "passive"))
      (node (ref "U$2") (pin "BS2") (pinfunction "1_BS2") (pintype "bidirectional"))
    )
    (net (code "50") (name "/RETURN") (class "Default")
      (node (ref "E14") (pin "5") (pinfunction "I3_5") (pintype "input"))
      (node (ref "E14") (pin "8") (pinfunction "O_8") (pintype "output"))
      (node (ref "U$2") (pin "AR2") (pinfunction "1_AR2") (pintype "bidirectional"))
    )
    (net (code "51") (name "/RUN") (class "Default")
      (node (ref "E18") (pin "3") (pinfunction "I_3") (pintype "input"))
      (node (ref "E40") (pin "12") (pinfunction "D_12") (pintype "input"))
      (node (ref "E40") (pin "5") (pinfunction "Q_5") (pintype "output"))
    )
    (net (code "52") (name "/SET_TS4") (class "Default")
      (node (ref "E26") (pin "1") (pinfunction "CLR_1") (pintype "input"))
      (node (ref "E27") (pin "13") (pinfunction "O_13") (pintype "output"))
      (node (ref "E38") (pin "2") (pinfunction "I1_2") (pintype "input"))
      (node (ref "E47") (pin "10") (pinfunction "I1_10") (pintype "input"))
    )
    (net (code "53") (name "/SOURCE") (class "Default")
      (node (ref "E01") (pin "6") (pinfunction "O_6") (pintype "output"))
      (node (ref "E01") (pin "9") (pinfunction "I0_9") (pintype "input"))
      (node (ref "U$2") (pin "AL2") (pinfunction "1_AL2") (pintype "bidirectional"))
    )
    (net (code "54") (name "/STROBE") (class "Default")
      (node (ref "E05") (pin "4") (pinfunction "I2_4") (pintype "input"))
      (node (ref "E05") (pin "5") (pinfunction "I3_5") (pintype "input"))
      (node (ref "E05") (pin "8") (pinfunction "O_8") (pintype "output"))
      (node (ref "U$2") (pin "AM2") (pinfunction "1_AM2") (pintype "bidirectional"))
    )
    (net (code "55") (name "/SW") (class "Default")
      (node (ref "D8") (pin "C") (pinfunction "C_C") (pintype "passive"))
      (node (ref "U$2") (pin "DV2") (pinfunction "1_DV2") (pintype "bidirectional"))
    )
    (net (code "56") (name "/TP1") (class "Default")
      (node (ref "E08") (pin "3") (pinfunction "I0_3") (pintype "input"))
      (node (ref "E08") (pin "4") (pinfunction "I1_4") (pintype "input"))
      (node (ref "E24") (pin "6") (pinfunction "O_6") (pintype "output"))
      (node (ref "E31") (pin "3") (pinfunction "CLK_3") (pintype "input"))
      (node (ref "R4") (pin "1") (pinfunction "1_1") (pintype "passive"))
      (node (ref "U$2") (pin "CD2") (pinfunction "1_CD2") (pintype "bidirectional"))
    )
    (net (code "57") (name "/TP2") (class "Default")
      (node (ref "E23") (pin "5") (pinfunction "I1_5") (pintype "input"))
      (node (ref "E28") (pin "8") (pinfunction "O_8") (pintype "output"))
      (node (ref "E30") (pin "3") (pinfunction "CLK_3") (pintype "input"))
      (node (ref "R10") (pin "1") (pinfunction "1_1") (pintype "passive"))
      (node (ref "U$2") (pin "CE2") (pinfunction "1_CE2") (pintype "bidirectional"))
    )
    (net (code "58") (name "/TP3") (class "Default")
      (node (ref "E08") (pin "1") (pinfunction "I0_1") (pintype "input"))
      (node (ref "E17") (pin "11") (pinfunction "I0_11") (pintype "input"))
      (node (ref "E17") (pin "9") (pinfunction "I1_9") (pintype "input"))
      (node (ref "E28") (pin "6") (pinfunction "O_6") (pintype "output"))
      (node (ref "E32") (pin "10") (pinfunction "B_10") (pintype "input"))
      (node (ref "E40") (pin "13") (pinfunction "CLR_13") (pintype "input"))
      (node (ref "E40") (pin "3") (pinfunction "CLK_3") (pintype "input"))
      (node (ref "R14") (pin "1") (pinfunction "1_1") (pintype "passive"))
      (node (ref "U$2") (pin "CH2") (pinfunction "1_CH2") (pintype "bidirectional"))
    )
    (net (code "59") (name "/TP4") (class "Default")
      (node (ref "E33") (pin "8") (pinfunction "O_8") (pintype "output"))
      (node (ref "R17") (pin "1") (pinfunction "1_1") (pintype "passive"))
      (node (ref "U$2") (pin "CJ2") (pinfunction "1_CJ2") (pintype "bidirectional"))
    )
    (net (code "60") (name "/TS1") (class "Default")
      (node (ref "E33") (pin "1") (pinfunction "I0_1") (pintype "input"))
      (node (ref "E48") (pin "13") (pinfunction "I2_13") (pintype "input"))
      (node (ref "E48") (pin "8") (pinfunction "O_8") (pintype "output"))
    )
    (net (code "61") (name "/USER_MODE") (class "Default")
      (node (ref "E07") (pin "2") (pinfunction "I1_2") (pintype "input"))
      (node (ref "E18") (pin "5") (pinfunction "I_5") (pintype "input"))
      (node (ref "U$2") (pin "DM2") (pinfunction "1_DM2") (pintype "bidirectional"))
    )
    (net (code "62") (name "/WRITE") (class "Default")
      (node (ref "E19") (pin "10") (pinfunction "I1_10") (pintype "input"))
      (node (ref "E19") (pin "12") (pinfunction "I2_12") (pintype "input"))
      (node (ref "E19") (pin "6") (pinfunction "O_6") (pintype "output"))
      (node (ref "E19") (pin "9") (pinfunction "I0_9") (pintype "input"))
      (node (ref "U$2") (pin "AS2") (pinfunction "1_AS2") (pintype "bidirectional"))
    )
    (net (code "63") (name "/~{BK_CYCLE}") (class "Default")
      (node (ref "D5") (pin "C") (pinfunction "C_C") (pintype "passive"))
      (node (ref "U$2") (pin "BL2") (pinfunction "1_BL2") (pintype "bidirectional"))
    )
    (net (code "64") (name "/~{BK_IN_PROG}") (class "Default")
      (node (ref "D4") (pin "C") (pinfunction "C_C") (pintype "passive"))
      (node (ref "U$2") (pin "BE2") (pinfunction "1_BE2") (pintype "bidirectional"))
    )
    (net (code "65") (name "/~{BUS_STROBE}") (class "Default")
      (node (ref "E17") (pin "1") (pinfunction "O_1") (pintype "open_collector"))
      (node (ref "E17") (pin "4") (pinfunction "O_4") (pintype "open_collector"))
      (node (ref "E37") (pin "3") (pinfunction "I_3") (pintype "input"))
      (node (ref "R20") (pin "1") (pinfunction "1_1") (pintype "passive"))
      (node (ref "R21") (pin "2") (pinfunction "2_2") (pintype "passive"))
      (node (ref "U$2") (pin "CK1") (pinfunction "1_CK1") (pintype "bidirectional"))
    )
    (net (code "66") (name "/~{C0}") (class "Default")
      (node (ref "E37") (pin "12") (pinfunction "O_12") (pintype "open_collector"))
      (node (ref "U$2") (pin "CE1") (pinfunction "1_CE1") (pintype "bidirectional"))
    )
    (net (code "67") (name "/~{C1}") (class "Default")
      (node (ref "E37") (pin "10") (pinfunction "O_10") (pintype "open_collector"))
      (node (ref "U$2") (pin "CH1") (pinfunction "1_CH1") (pintype "bidirectional"))
    )
    (net (code "68") (name "/~{CAF}") (class "Default")
      (node (ref "E32") (pin "9") (pinfunction "A_9") (pintype "input"))
      (node (ref "E50") (pin "12") (pinfunction "1_12") (pintype "output"))
    )
    (net (code "69") (name "/~{DATA00}") (class "Default")
      (node (ref "E13") (pin "4") (pinfunction "I0_4") (pintype "input"))
      (node (ref "E41") (pin "13") (pinfunction "O_13") (pintype "open_collector"))
      (node (ref "U$2") (pin "AR1") (pinfunction "1_AR1") (pintype "bidirectional"))
    )
    (net (code "70") (name "/~{DATA02}") (class "Default")
      (node (ref "E36") (pin "1") (pinfunction "O_1") (pintype "open_collector"))
      (node (ref "U$2") (pin "AU1") (pinfunction "1_AU1") (pintype "bidirectional"))
    )
    (net (code "71") (name "/~{DATA04}") (class "Default")
      (node (ref "E41") (pin "10") (pinfunction "O_10") (pintype "open_collector"))
      (node (ref "U$2") (pin "BR1") (pinfunction "1_BR1") (pintype "bidirectional"))
    )
    (net (code "72") (name "/~{DEFER}") (class "Default")
      (node (ref "E22") (pin "5") (pinfunction "I0_5") (pintype "input"))
      (node (ref "U$2") (pin "DK2") (pinfunction "1_DK2") (pintype "bidirectional"))
    )
    (net (code "73") (name "/~{EMA0}") (class "Default")
      (node (ref "D1") (pin "C") (pinfunction "C_C") (pintype "passive"))
      (node (ref "U$2") (pin "AD2") (pinfunction "1_AD2") (pintype "bidirectional"))
    )
    (net (code "74") (name "/~{EMA1}") (class "Default")
      (node (ref "D2") (pin "C") (pinfunction "C_C") (pintype "passive"))
      (node (ref "U$2") (pin "AE2") (pinfunction "1_AE2") (pintype "bidirectional"))
    )
    (net (code "75") (name "/~{EMA2}") (class "Default")
      (node (ref "D3") (pin "C") (pinfunction "C_C") (pintype "passive"))
      (node (ref "U$2") (pin "AH2") (pinfunction "1_AH2") (pintype "bidirectional"))
    )
    (net (code "76") (name "/~{FAST}") (class "Default")
      (node (ref "E30") (pin "12") (pinfunction "D_12") (pintype "input"))
      (node (ref "E30") (pin "2") (pinfunction "D_2") (pintype "input"))
      (node (ref "E31") (pin "5") (pinfunction "Q_5") (pintype "output"))
    )
    (net (code "77") (name "/~{FAULT}") (class "Default")
      (node (ref "E01") (pin "10") (pinfunction "I1_10") (pintype "input"))
      (node (ref "E05") (pin "2") (pinfunction "I1_2") (pintype "input"))
      (node (ref "E10") (pin "12") (pinfunction "I2_12") (pintype "input"))
      (node (ref "E14") (pin "4") (pinfunction "I2_4") (pintype "input"))
      (node (ref "E19") (pin "1") (pinfunction "I0_1") (pintype "input"))
      (node (ref "E21") (pin "10") (pinfunction "PRE_10") (pintype "input"))
      (node (ref "E21") (pin "4") (pinfunction "PRE_4") (pintype "input"))
      (node (ref "E35") (pin "5") (pinfunction "I_5") (pintype "input"))
      (node (ref "E38") (pin "10") (pinfunction "I1_10") (pintype "input"))
      (node (ref "E38") (pin "13") (pinfunction "I3_13") (pintype "input"))
      (node (ref "E38") (pin "4") (pinfunction "I2_4") (pintype "input"))
      (node (ref "E38") (pin "5") (pinfunction "I3_5") (pintype "input"))
      (node (ref "E40") (pin "1") (pinfunction "CLR_1") (pintype "input"))
      (node (ref "E43") (pin "2") (pinfunction "I1_2") (pintype "input"))
      (node (ref "E43") (pin "4") (pinfunction "I2_4") (pintype "input"))
      (node (ref "E43") (pin "8") (pinfunction "O_8") (pintype "output"))
      (node (ref "E48") (pin "9") (pinfunction "I0_9") (pintype "input"))
      (node (ref "U$2") (pin "DB1") (pinfunction "1_DB1") (pintype "bidirectional"))
    )
    (net (code "78") (name "/~{FETCH}") (class "Default")
      (node (ref "E18") (pin "1") (pinfunction "I_1") (pintype "input"))
      (node (ref "U$2") (pin "DJ2") (pinfunction "1_DJ2") (pintype "bidirectional"))
    )
    (net (code "79") (name "/~{F_SET}") (class "Default")
      (node (ref "E42") (pin "11") (pinfunction "I_11") (pintype "input"))
      (node (ref "U$2") (pin "DP2") (pinfunction "1_DP2") (pintype "bidirectional"))
    )
    (net (code "80") (name "/~{GTF}") (class "Default")
      (node (ref "E23") (pin "1") (pinfunction "I0_1") (pintype "input"))
      (node (ref "E37") (pin "11") (pinfunction "I_11") (pintype "input"))
      (node (ref "E37") (pin "13") (pinfunction "I_13") (pintype "input"))
      (node (ref "E50") (pin "11") (pinfunction "2_11") (pintype "output"))
    )
    (net (code "81") (name "/~{INTERNAL_IO}") (class "Default")
      (node (ref "D13") (pin "C") (pinfunction "C_C") (pintype "passive"))
      (node (ref "E37") (pin "6") (pinfunction "O_6") (pintype "open_collector"))
      (node (ref "U$2") (pin "CL1") (pinfunction "1_CL1") (pintype "bidirectional"))
    )
    (net (code "82") (name "/~{INT_RQ}") (class "Default")
      (node (ref "E42") (pin "9") (pinfunction "I_9") (pintype "input"))
      (node (ref "U$2") (pin "CP1") (pinfunction "1_CP1") (pintype "bidirectional"))
    )
    (net (code "83") (name "/~{IOF}") (class "Default")
      (node (ref "E46") (pin "2") (pinfunction "I1_2") (pintype "input"))
      (node (ref "E50") (pin "9") (pinfunction "4_9") (pintype "output"))
    )
    (net (code "84") (name "/~{ION}") (class "Default")
      (node (ref "E46") (pin "5") (pinfunction "I3_5") (pintype "input"))
      (node (ref "E50") (pin "5") (pinfunction "7_5") (pintype "output"))
    )
    (net (code "85") (name "/~{IO_PAUSE}") (class "Default")
      (node (ref "E07") (pin "6") (pinfunction "O_6") (pintype "output"))
      (node (ref "E18") (pin "11") (pinfunction "I_11") (pintype "input"))
      (node (ref "E22") (pin "11") (pinfunction "I0_11") (pintype "input"))
      (node (ref "R28") (pin "1") (pinfunction "1_1") (pintype "passive"))
      (node (ref "U$2") (pin "CD1") (pinfunction "1_CD1") (pintype "bidirectional"))
    )
    (net (code "86") (name "/~{KEY_CONTROL}") (class "Default")
      (node (ref "E35") (pin "13") (pinfunction "I_13") (pintype "input"))
      (node (ref "E35") (pin "3") (pinfunction "I_3") (pintype "input"))
      (node (ref "U$2") (pin "DU2") (pinfunction "1_DU2") (pintype "bidirectional"))
    )
    (net (code "87") (name "/~{LINK_DATA}") (class "Default")
      (node (ref "E36") (pin "4") (pinfunction "O_4") (pintype "open_collector"))
      (node (ref "U$2") (pin "CR2") (pinfunction "1_CR2") (pintype "bidirectional"))
    )
    (net (code "88") (name "/~{LINK_LOAD}") (class "Default")
      (node (ref "E17") (pin "10") (pinfunction "O_10") (pintype "open_collector"))
      (node (ref "E17") (pin "13") (pinfunction "O_13") (pintype "open_collector"))
      (node (ref "R34") (pin "2") (pinfunction "2_2") (pintype "passive"))
      (node (ref "R35") (pin "1") (pinfunction "1_1") (pintype "passive"))
      (node (ref "U$2") (pin "CS2") (pinfunction "1_CS2") (pintype "bidirectional"))
    )
    (net (code "89") (name "/~{LINK}") (class "Default")
      (node (ref "E18") (pin "9") (pinfunction "I_9") (pintype "input"))
      (node (ref "U$2") (pin "AV2") (pinfunction "1_AV2") (pintype "bidirectional"))
    )
    (net (code "90") (name "/~{MA00}") (class "Default")
      (node (ref "E12") (pin "12") (pinfunction "I7_12") (pintype "input"))
      (node (ref "U$2") (pin "AD1") (pinfunction "1_AD1") (pintype "bidirectional"))
    )
    (net (code "91") (name "/~{MA01}") (class "Default")
      (node (ref "E12") (pin "11") (pinfunction "I6_11") (pintype "input"))
      (node (ref "U$2") (pin "AE1") (pinfunction "1_AE1") (pintype "bidirectional"))
    )
    (net (code "92") (name "/~{MA02}") (class "Default")
      (node (ref "E12") (pin "1") (pinfunction "I0_1") (pintype "input"))
      (node (ref "U$2") (pin "AH1") (pinfunction "1_AH1") (pintype "bidirectional"))
    )
    (net (code "93") (name "/~{MA03}") (class "Default")
      (node (ref "E12") (pin "2") (pinfunction "I1_2") (pintype "input"))
      (node (ref "U$2") (pin "AJ1") (pinfunction "1_AJ1") (pintype "bidirectional"))
    )
    (net (code "94") (name "/~{MA04}") (class "Default")
      (node (ref "E12") (pin "6") (pinfunction "I5_6") (pintype "input"))
      (node (ref "U$2") (pin "BD1") (pinfunction "1_BD1") (pintype "bidirectional"))
    )
    (net (code "95") (name "/~{MA05}") (class "Default")
      (node (ref "E12") (pin "5") (pinfunction "I4_5") (pintype "input"))
      (node (ref "U$2") (pin "BE1") (pinfunction "1_BE1") (pintype "bidirectional"))
    )
    (net (code "96") (name "/~{MA06}") (class "Default")
      (node (ref "E12") (pin "4") (pinfunction "I3_4") (pintype "input"))
      (node (ref "U$2") (pin "BH1") (pinfunction "1_BH1") (pintype "bidirectional"))
    )
    (net (code "97") (name "/~{MA07}") (class "Default")
      (node (ref "E12") (pin "3") (pinfunction "I2_3") (pintype "input"))
      (node (ref "U$2") (pin "BJ1") (pinfunction "1_BJ1") (pintype "bidirectional"))
    )
    (net (code "98") (name "/~{MA08}") (class "Default")
      (node (ref "E22") (pin "9") (pinfunction "I1_9") (pintype "input"))
      (node (ref "U$2") (pin "DD1") (pinfunction "1_DD1") (pintype "bidirectional"))
    )
    (net (code "99") (name "/~{MD00}") (class "Default")
      (node (ref "E04") (pin "6") (pinfunction "I2_6") (pintype "input"))
      (node (ref "E13") (pin "9") (pinfunction "I0_9") (pintype "input"))
      (node (ref "U$2") (pin "AK1") (pinfunction "1_AK1") (pintype "bidirectional"))
    )
    (net (code "100") (name "/~{MD01}") (class "Default")
      (node (ref "E04") (pin "5") (pinfunction "I1_5") (pintype "input"))
      (node (ref "E13") (pin "10") (pinfunction "I1_10") (pintype "input"))
      (node (ref "U$2") (pin "AL1") (pinfunction "1_AL1") (pintype "bidirectional"))
    )
    (net (code "101") (name "/~{MD02}") (class "Default")
      (node (ref "E04") (pin "4") (pinfunction "I0_4") (pintype "input"))
      (node (ref "E07") (pin "1") (pinfunction "I0_1") (pintype "input"))
      (node (ref "U$2") (pin "AM1") (pinfunction "1_AM1") (pintype "bidirectional"))
    )
    (net (code "102") (name "/~{MD03}") (class "Default")
      (node (ref "E04") (pin "9") (pinfunction "I3_9") (pintype "input"))
      (node (ref "E16") (pin "6") (pinfunction "I5_6") (pintype "input"))
      (node (ref "U$2") (pin "DK1") (pinfunction "1_DK1") (pintype "bidirectional"))
    )
    (net (code "103") (name "/~{MD04}") (class "Default")
      (node (ref "E16") (pin "5") (pinfunction "I4_5") (pintype "input"))
      (node (ref "U$2") (pin "BK1") (pinfunction "1_BK1") (pintype "bidirectional"))
    )
    (net (code "104") (name "/~{MD05}") (class "Default")
      (node (ref "E16") (pin "4") (pinfunction "I3_4") (pintype "input"))
      (node (ref "U$2") (pin "BL1") (pinfunction "1_BL1") (pintype "bidirectional"))
    )
    (net (code "105") (name "/~{MD06}") (class "Default")
      (node (ref "E16") (pin "3") (pinfunction "I2_3") (pintype "input"))
      (node (ref "U$2") (pin "BM1") (pinfunction "1_BM1") (pintype "bidirectional"))
    )
    (net (code "106") (name "/~{MD07}") (class "Default")
      (node (ref "E16") (pin "2") (pinfunction "I1_2") (pintype "input"))
      (node (ref "U$2") (pin "BP1") (pinfunction "1_BP1") (pintype "bidirectional"))
    )
    (net (code "107") (name "/~{MD08}") (class "Default")
      (node (ref "E16") (pin "1") (pinfunction "I0_1") (pintype "input"))
      (node (ref "U$2") (pin "AP1") (pinfunction "1_AP1") (pintype "bidirectional"))
    )
    (net (code "108") (name "/~{MD09}") (class "Default")
      (node (ref "E50") (pin "1") (pinfunction "C_1") (pintype "input"))
      (node (ref "U$2") (pin "DL1") (pinfunction "1_DL1") (pintype "bidirectional"))
    )
    (net (code "109") (name "/~{MD10}") (class "Default")
      (node (ref "E04") (pin "11") (pinfunction "I5_11") (pintype "input"))
      (node (ref "E50") (pin "14") (pinfunction "B_14") (pintype "input"))
      (node (ref "U$2") (pin "DM1") (pinfunction "1_DM1") (pintype "bidirectional"))
    )
    (net (code "110") (name "/~{MD11}") (class "Default")
      (node (ref "E42") (pin "13") (pinfunction "I_13") (pintype "input"))
      (node (ref "U$2") (pin "DP1") (pinfunction "1_DP1") (pintype "bidirectional"))
    )
    (net (code "111") (name "/~{MD_DIR}") (class "Default")
      (node (ref "E35") (pin "10") (pinfunction "O_10") (pintype "open_collector"))
      (node (ref "U$2") (pin "AK2") (pinfunction "1_AK2") (pintype "bidirectional"))
    )
    (net (code "112") (name "/~{MEM_START}") (class "Default")
      (node (ref "E40") (pin "4") (pinfunction "PRE_4") (pintype "input"))
      (node (ref "U$2") (pin "AJ2") (pinfunction "1_AJ2") (pintype "bidirectional"))
    )
    (net (code "113") (name "/~{NOT_LAST_XFR}") (class "Default")
      (node (ref "D10") (pin "C") (pinfunction "C_C") (pintype "passive"))
      (node (ref "E27") (pin "9") (pinfunction "I0_9") (pintype "input"))
      (node (ref "U$2") (pin "CM1") (pinfunction "1_CM1") (pintype "bidirectional"))
    )
    (net (code "114") (name "/~{NOT_LAST}") (class "Default")
      (node (ref "E17") (pin "2") (pinfunction "I0_2") (pintype "input"))
      (node (ref "E17") (pin "6") (pinfunction "I1_6") (pintype "input"))
      (node (ref "E21") (pin "2") (pinfunction "D_2") (pintype "input"))
      (node (ref "E26") (pin "12") (pinfunction "D_12") (pintype "input"))
      (node (ref "E27") (pin "14") (pinfunction "O_14") (pintype "output"))
    )
    (net (code "115") (name "/~{NS1400B}") (class "Default")
      (node (ref "E26") (pin "13") (pinfunction "CLR_13") (pintype "input"))
      (node (ref "E35") (pin "6") (pinfunction "O_6") (pintype "open_collector"))
      (node (ref "E35") (pin "8") (pinfunction "O_8") (pintype "open_collector"))
      (node (ref "R19") (pin "1") (pinfunction "1_1") (pintype "passive"))
    )
    (net (code "116") (name "/~{POWER_NOT_OK}") (class "Default")
      (node (ref "E09") (pin "13") (pinfunction "CLR_13") (pintype "input"))
      (node (ref "E27") (pin "2") (pinfunction "O_2") (pintype "output"))
      (node (ref "E31") (pin "10") (pinfunction "PRE_10") (pintype "input"))
      (node (ref "E32") (pin "2") (pinfunction "B_2") (pintype "input"))
      (node (ref "E32") (pin "3") (pinfunction "CLR_3") (pintype "input"))
      (node (ref "E35") (pin "1") (pinfunction "I_1") (pintype "input"))
      (node (ref "E36") (pin "11") (pinfunction "I0_11") (pintype "input"))
      (node (ref "E36") (pin "12") (pinfunction "I1_12") (pintype "input"))
    )
    (net (code "117") (name "/~{RTF}") (class "Default")
      (node (ref "E42") (pin "5") (pinfunction "I_5") (pintype "input"))
      (node (ref "E46") (pin "1") (pinfunction "I0_1") (pintype "input"))
      (node (ref "E50") (pin "10") (pinfunction "3_10") (pintype "output"))
      (node (ref "J") (pin "F1") (pinfunction "1_F1") (pintype "bidirectional"))
    )
    (net (code "118") (name "/~{RUN}") (class "Default")
      (node (ref "E18") (pin "4") (pinfunction "O_4") (pintype "output"))
      (node (ref "R39") (pin "1") (pinfunction "1_1") (pintype "passive"))
      (node (ref "U$2") (pin "BU2") (pinfunction "1_BU2") (pintype "bidirectional"))
    )
    (net (code "119") (name "/~{SGT}") (class "Default")
      (node (ref "E50") (pin "13") (pinfunction "0_13") (pintype "output"))
      (node (ref "J") (pin "D1") (pinfunction "1_D1") (pintype "bidirectional"))
    )
    (net (code "120") (name "/~{SKIP}") (class "Default")
      (node (ref "E41") (pin "1") (pinfunction "O_1") (pintype "open_collector"))
      (node (ref "E41") (pin "4") (pinfunction "O_4") (pintype "open_collector"))
      (node (ref "U$2") (pin "CS1") (pinfunction "1_CS1") (pintype "bidirectional"))
    )
    (net (code "121") (name "/~{SKON}") (class "Default")
      (node (ref "E42") (pin "1") (pinfunction "I_1") (pintype "input"))
      (node (ref "E46") (pin "4") (pinfunction "I2_4") (pintype "input"))
      (node (ref "E50") (pin "4") (pinfunction "6_4") (pintype "output"))
    )
    (net (code "122") (name "/~{SRQ}") (class "Default")
      (node (ref "E42") (pin "3") (pinfunction "I_3") (pintype "input"))
      (node (ref "E50") (pin "3") (pinfunction "5_3") (pintype "output"))
    )
    (net (code "123") (name "/~{STALL}") (class "Default")
      (node (ref "D6") (pin "C") (pinfunction "C_C") (pintype "passive"))
      (node (ref "E13") (pin "6") (pinfunction "I0_6") (pintype "input"))
      (node (ref "U$2") (pin "BR2") (pinfunction "1_BR2") (pintype "bidirectional"))
    )
    (net (code "124") (name "/~{STOP}") (class "Default")
      (node (ref "E35") (pin "2") (pinfunction "O_2") (pintype "open_collector"))
      (node (ref "E35") (pin "4") (pinfunction "O_4") (pintype "open_collector"))
      (node (ref "E36") (pin "10") (pinfunction "O_10") (pintype "open_collector"))
      (node (ref "E40") (pin "2") (pinfunction "D_2") (pintype "input"))
      (node (ref "U$2") (pin "DS2") (pinfunction "1_DS2") (pintype "bidirectional"))
    )
    (net (code "125") (name "/~{STROBE}") (class "Default")
      (node (ref "E05") (pin "10") (pinfunction "I1_10") (pintype "input"))
      (node (ref "E05") (pin "12") (pinfunction "I2_12") (pintype "input"))
      (node (ref "E05") (pin "6") (pinfunction "O_6") (pintype "output"))
      (node (ref "E05") (pin "9") (pinfunction "I0_9") (pintype "input"))
      (node (ref "E26") (pin "3") (pinfunction "CLK_3") (pintype "input"))
    )
    (net (code "126") (name "/~{TS1}") (class "Default")
      (node (ref "E33") (pin "6") (pinfunction "O_6") (pintype "output"))
      (node (ref "E48") (pin "10") (pinfunction "I1_10") (pintype "input"))
      (node (ref "R3") (pin "1") (pinfunction "1_1") (pintype "passive"))
      (node (ref "U$2") (pin "CK2") (pinfunction "1_CK2") (pintype "bidirectional"))
    )
    (net (code "127") (name "/~{TS2}") (class "Default")
      (node (ref "E38") (pin "8") (pinfunction "O_8") (pintype "output"))
      (node (ref "E47") (pin "2") (pinfunction "I1_2") (pintype "input"))
      (node (ref "R9") (pin "1") (pinfunction "1_1") (pintype "passive"))
      (node (ref "U$2") (pin "CL2") (pinfunction "1_CL2") (pintype "bidirectional"))
    )
    (net (code "128") (name "/~{TS3}") (class "Default")
      (node (ref "E38") (pin "6") (pinfunction "O_6") (pintype "output"))
      (node (ref "E47") (pin "12") (pinfunction "I0_12") (pintype "input"))
      (node (ref "R13") (pin "1") (pinfunction "1_1") (pintype "passive"))
      (node (ref "U$2") (pin "CM2") (pinfunction "1_CM2") (pintype "bidirectional"))
    )
    (net (code "129") (name "/~{TS4}") (class "Default")
      (node (ref "E43") (pin "6") (pinfunction "O_6") (pintype "output"))
      (node (ref "E47") (pin "9") (pinfunction "I0_9") (pintype "input"))
      (node (ref "R16") (pin "1") (pinfunction "1_1") (pintype "passive"))
      (node (ref "U$2") (pin "CP2") (pinfunction "1_CP2") (pintype "bidirectional"))
    )
    (net (code "130") (name "/~{USER_MODE}") (class "Default")
      (node (ref "E04") (pin "12") (pinfunction "I6_12") (pintype "input"))
      (node (ref "E18") (pin "6") (pinfunction "O_6") (pintype "output"))
      (node (ref "R38") (pin "1") (pinfunction "1_1") (pintype "passive"))
    )
    (net (code "131") (name "GND") (class "Default")
      (node (ref "C1") (pin "2") (pinfunction "2_2") (pintype "passive"))
      (node (ref "C10") (pin "2") (pinfunction "2_2") (pintype "passive"))
      (node (ref "C11") (pin "2") (pinfunction "2_2") (pintype "passive"))
      (node (ref "C12") (pin "2") (pinfunction "2_2") (pintype "passive"))
      (node (ref "C13") (pin "2") (pinfunction "2_2") (pintype "passive"))
      (node (ref "C14") (pin "2") (pinfunction "2_2") (pintype "passive"))
      (node (ref "C15") (pin "2") (pinfunction "2_2") (pintype "passive"))
      (node (ref "C16") (pin "2") (pinfunction "2_2") (pintype "passive"))
      (node (ref "C17") (pin "2") (pinfunction "2_2") (pintype "passive"))
      (node (ref "C18") (pin "2") (pinfunction "2_2") (pintype "passive"))
      (node (ref "C19") (pin "2") (pinfunction "2_2") (pintype "passive"))
      (node (ref "C2") (pin "2") (pinfunction "2_2") (pintype "passive"))
      (node (ref "C20") (pin "2") (pinfunction "2_2") (pintype "passive"))
      (node (ref "C21") (pin "2") (pinfunction "2_2") (pintype "passive"))
      (node (ref "C22") (pin "2") (pinfunction "2_2") (pintype "passive"))
      (node (ref "C23") (pin "2") (pinfunction "2_2") (pintype "passive"))
      (node (ref "C24") (pin "2") (pinfunction "2_2") (pintype "passive"))
      (node (ref "C25") (pin "2") (pinfunction "2_2") (pintype "passive"))
      (node (ref "C26") (pin "2") (pinfunction "2_2") (pintype "passive"))
      (node (ref "C27") (pin "2") (pinfunction "2_2") (pintype "passive"))
      (node (ref "C28") (pin "2") (pinfunction "2_2") (pintype "passive"))
      (node (ref "C29") (pin "2") (pinfunction "2_2") (pintype "passive"))
      (node (ref "C3") (pin "2") (pinfunction "2_2") (pintype "passive"))
      (node (ref "C30") (pin "2") (pinfunction "2_2") (pintype "passive"))
      (node (ref "C31") (pin "2") (pinfunction "2_2") (pintype "passive"))
      (node (ref "C32") (pin "2") (pinfunction "2_2") (pintype "passive"))
      (node (ref "C33") (pin "2") (pinfunction "2_2") (pintype "passive"))
      (node (ref "C34") (pin "2") (pinfunction "2_2") (pintype "passive"))
      (node (ref "C36") (pin "-") (pinfunction "-_-") (pintype "passive"))
      (node (ref "C37") (pin "-") (pinfunction "-_-") (pintype "passive"))
      (node (ref "C38") (pin "-") (pinfunction "-_-") (pintype "passive"))
      (node (ref "C4") (pin "2") (pinfunction "2_2") (pintype "passive"))
      (node (ref "C41") (pin "2") (pinfunction "2_2") (pintype "passive"))
      (node (ref "C42") (pin "2") (pinfunction "2_2") (pintype "passive"))
      (node (ref "C44") (pin "2") (pinfunction "2_2") (pintype "passive"))
      (node (ref "C47") (pin "2") (pinfunction "2_2") (pintype "passive"))
      (node (ref "C49") (pin "2") (pinfunction "2_2") (pintype "passive"))
      (node (ref "C5") (pin "2") (pinfunction "2_2") (pintype "passive"))
      (node (ref "C50") (pin "2") (pinfunction "2_2") (pintype "passive"))
      (node (ref "C6") (pin "2") (pinfunction "2_2") (pintype "passive"))
      (node (ref "C7") (pin "2") (pinfunction "2_2") (pintype "passive"))
      (node (ref "C8") (pin "2") (pinfunction "2_2") (pintype "passive"))
      (node (ref "C9") (pin "2") (pinfunction "2_2") (pintype "passive"))
      (node (ref "D1") (pin "A") (pinfunction "A_A") (pintype "passive"))
      (node (ref "D10") (pin "A") (pinfunction "A_A") (pintype "passive"))
      (node (ref "D11") (pin "A") (pinfunction "A_A") (pintype "passive"))
      (node (ref "D13") (pin "A") (pinfunction "A_A") (pintype "passive"))
      (node (ref "D2") (pin "A") (pinfunction "A_A") (pintype "passive"))
      (node (ref "D3") (pin "A") (pinfunction "A_A") (pintype "passive"))
      (node (ref "D4") (pin "A") (pinfunction "A_A") (pintype "passive"))
      (node (ref "D5") (pin "A") (pinfunction "A_A") (pintype "passive"))
      (node (ref "D6") (pin "A") (pinfunction "A_A") (pintype "passive"))
      (node (ref "D7") (pin "A") (pinfunction "A_A") (pintype "passive"))
      (node (ref "D8") (pin "A") (pinfunction "A_A") (pintype "passive"))
      (node (ref "D9") (pin "C") (pinfunction "C_C") (pintype "passive"))
      (node (ref "E02") (pin "10") (pinfunction "S1_10") (pintype "input"))
      (node (ref "E02") (pin "3") (pinfunction "A_3") (pintype "input"))
      (node (ref "E02") (pin "4") (pinfunction "B_4") (pintype "input"))
      (node (ref "E02") (pin "5") (pinfunction "C_5") (pintype "input"))
      (node (ref "E02") (pin "6") (pinfunction "D_6") (pintype "input"))
      (node (ref "E02") (pin "7") (pinfunction "SL_7") (pintype "input"))
      (node (ref "E06") (pin "3") (pinfunction "A_3") (pintype "input"))
      (node (ref "E06") (pin "4") (pinfunction "B_4") (pintype "input"))
      (node (ref "E06") (pin "7") (pinfunction "SL_7") (pintype "input"))
      (node (ref "E11") (pin "10") (pinfunction "S1_10") (pintype "input"))
      (node (ref "E11") (pin "3") (pinfunction "A_3") (pintype "input"))
      (node (ref "E11") (pin "4") (pinfunction "B_4") (pintype "input"))
      (node (ref "E11") (pin "5") (pinfunction "C_5") (pintype "input"))
      (node (ref "E11") (pin "6") (pinfunction "D_6") (pintype "input"))
      (node (ref "E11") (pin "7") (pinfunction "SL_7") (pintype "input"))
      (node (ref "E13") (pin "5") (pinfunction "I1_5") (pintype "input"))
      (node (ref "E13") (pin "7") (pinfunction "I1_7") (pintype "input"))
      (node (ref "E15") (pin "10") (pinfunction "S1_10") (pintype "input"))
      (node (ref "E15") (pin "3") (pinfunction "A_3") (pintype "input"))
      (node (ref "E15") (pin "4") (pinfunction "B_4") (pintype "input"))
      (node (ref "E15") (pin "5") (pinfunction "C_5") (pintype "input"))
      (node (ref "E15") (pin "6") (pinfunction "D_6") (pintype "input"))
      (node (ref "E15") (pin "7") (pinfunction "SL_7") (pintype "input"))
      (node (ref "E20") (pin "10") (pinfunction "S1_10") (pintype "input"))
      (node (ref "E20") (pin "3") (pinfunction "A_3") (pintype "input"))
      (node (ref "E20") (pin "4") (pinfunction "B_4") (pintype "input"))
      (node (ref "E20") (pin "5") (pinfunction "C_5") (pintype "input"))
      (node (ref "E20") (pin "6") (pinfunction "D_6") (pintype "input"))
      (node (ref "E20") (pin "7") (pinfunction "SL_7") (pintype "input"))
      (node (ref "E25") (pin "7") (pinfunction "SL_7") (pintype "input"))
      (node (ref "E27") (pin "10") (pinfunction "I1_10") (pintype "input"))
      (node (ref "E27") (pin "6") (pinfunction "I0_6") (pintype "input"))
      (node (ref "E29") (pin "10") (pinfunction "S1_10") (pintype "input"))
      (node (ref "E29") (pin "3") (pinfunction "A_3") (pintype "input"))
      (node (ref "E29") (pin "4") (pinfunction "B_4") (pintype "input"))
      (node (ref "E29") (pin "5") (pinfunction "C_5") (pintype "input"))
      (node (ref "E29") (pin "6") (pinfunction "D_6") (pintype "input"))
      (node (ref "E29") (pin "7") (pinfunction "SL_7") (pintype "input"))
      (node (ref "E31") (pin "12") (pinfunction "D_12") (pintype "input"))
      (node (ref "E32") (pin "1") (pinfunction "A_1") (pintype "input"))
      (node (ref "E34") (pin "10") (pinfunction "S1_10") (pintype "input"))
      (node (ref "E34") (pin "3") (pinfunction "A_3") (pintype "input"))
      (node (ref "E34") (pin "4") (pinfunction "B_4") (pintype "input"))
      (node (ref "E34") (pin "5") (pinfunction "C_5") (pintype "input"))
      (node (ref "E34") (pin "6") (pinfunction "D_6") (pintype "input"))
      (node (ref "E34") (pin "7") (pinfunction "SL_7") (pintype "input"))
      (node (ref "E39") (pin "10") (pinfunction "S1_10") (pintype "input"))
      (node (ref "E39") (pin "3") (pinfunction "A_3") (pintype "input"))
      (node (ref "E39") (pin "4") (pinfunction "B_4") (pintype "input"))
      (node (ref "E39") (pin "5") (pinfunction "C_5") (pintype "input"))
      (node (ref "E39") (pin "6") (pinfunction "D_6") (pintype "input"))
      (node (ref "E39") (pin "7") (pinfunction "SL_7") (pintype "input"))
      (node (ref "E44") (pin "3") (pinfunction "A_3") (pintype "input"))
      (node (ref "E44") (pin "4") (pinfunction "B_4") (pintype "input"))
      (node (ref "E44") (pin "7") (pinfunction "SL_7") (pintype "input"))
      (node (ref "E49") (pin "11") (pinfunction "CLK_11") (pintype "input"))
      (node (ref "E49") (pin "12") (pinfunction "D_12") (pintype "input"))
      (node (ref "J") (pin "C1") (pinfunction "1_C1") (pintype "bidirectional"))
      (node (ref "J") (pin "C2") (pinfunction "1_C2") (pintype "bidirectional"))
      (node (ref "J") (pin "E1") (pinfunction "1_E1") (pintype "bidirectional"))
      (node (ref "J") (pin "E2") (pinfunction "1_E2") (pintype "bidirectional"))
      (node (ref "J") (pin "H1") (pinfunction "1_H1") (pintype "bidirectional"))
      (node (ref "J") (pin "H2") (pinfunction "1_H2") (pintype "bidirectional"))
      (node (ref "J") (pin "N2") (pinfunction "1_N2") (pintype "bidirectional"))
      (node (ref "J") (pin "R1") (pinfunction "1_R1") (pintype "bidirectional"))
      (node (ref "J") (pin "R2") (pinfunction "1_R2") (pintype "bidirectional"))
      (node (ref "J") (pin "T1") (pinfunction "1_T1") (pintype "bidirectional"))
      (node (ref "J") (pin "T2") (pinfunction "1_T2") (pintype "bidirectional"))
      (node (ref "R21") (pin "1") (pinfunction "1_1") (pintype "passive"))
      (node (ref "R25") (pin "1") (pinfunction "1_1") (pintype "passive"))
      (node (ref "R34") (pin "1") (pinfunction "1_1") (pintype "passive"))
      (node (ref "T1") (pin "13") (pinfunction "13_13") (pintype "passive"))
      (node (ref "T1") (pin "9") (pinfunction "9_9") (pintype "passive"))
      (node (ref "U$2") (pin "AC2") (pinfunction "1_AC2") (pintype "bidirectional"))
      (node (ref "U$2") (pin "AF1") (pinfunction "1_AF1") (pintype "bidirectional"))
      (node (ref "U$2") (pin "AN1") (pinfunction "1_AN1") (pintype "bidirectional"))
      (node (ref "U$2") (pin "AN2") (pinfunction "1_AN2") (pintype "bidirectional"))
      (node (ref "U$2") (pin "AT1") (pinfunction "1_AT1") (pintype "bidirectional"))
      (node (ref "U$2") (pin "BC2") (pinfunction "1_BC2") (pintype "bidirectional"))
      (node (ref "U$2") (pin "BF1") (pinfunction "1_BF1") (pintype "bidirectional"))
      (node (ref "U$2") (pin "BN2") (pinfunction "1_BN2") (pintype "bidirectional"))
      (node (ref "U$2") (pin "BT1") (pinfunction "1_BT1") (pintype "bidirectional"))
      (node (ref "U$2") (pin "BT2") (pinfunction "1_BT2") (pintype "bidirectional"))
      (node (ref "U$2") (pin "CC1") (pinfunction "1_CC1") (pintype "bidirectional"))
      (node (ref "U$2") (pin "CC2") (pinfunction "1_CC2") (pintype "bidirectional"))
      (node (ref "U$2") (pin "CF2") (pinfunction "1_CF2") (pintype "bidirectional"))
      (node (ref "U$2") (pin "CN1") (pinfunction "1_CN1") (pintype "bidirectional"))
      (node (ref "U$2") (pin "CT1") (pinfunction "1_CT1") (pintype "bidirectional"))
      (node (ref "U$2") (pin "DC1") (pinfunction "1_DC1") (pintype "bidirectional"))
      (node (ref "U$2") (pin "DF1") (pinfunction "1_DF1") (pintype "bidirectional"))
      (node (ref "U$2") (pin "DN1") (pinfunction "1_DN1") (pintype "bidirectional"))
      (node (ref "U$2") (pin "DT1") (pinfunction "1_DT1") (pintype "bidirectional"))
      (node (ref "U$2") (pin "DT2") (pinfunction "1_DT2") (pintype "bidirectional"))
      (node (ref "W1") (pin "1") (pinfunction "1_1") (pintype "passive"))
      (node (ref "Y1A") (pin "1") (pinfunction "1_1") (pintype "passive"))
      (node (ref "Y1A") (pin "3") (pinfunction "3_3") (pintype "passive"))
      (node (ref "Y1B") (pin "7") (pinfunction "GND_7") (pintype "power_in"))
    )
    (net (code "132") (name "Net-(C42-Pad1)") (class "Default")
      (node (ref "C42") (pin "1") (pinfunction "1_1") (pintype "passive"))
      (node (ref "C43") (pin "2") (pinfunction "2_2") (pintype "passive"))
      (node (ref "Y1A") (pin "2") (pinfunction "2_2") (pintype "passive"))
    )
    (net (code "133") (name "Net-(C44-Pad1)") (class "Default")
      (node (ref "C44") (pin "1") (pinfunction "1_1") (pintype "passive"))
      (node (ref "C45") (pin "2") (pinfunction "2_2") (pintype "passive"))
    )
    (net (code "134") (name "Net-(C46-Pad2)") (class "Default")
      (node (ref "C46") (pin "2") (pinfunction "2_2") (pintype "passive"))
      (node (ref "R6") (pin "2") (pinfunction "2_2") (pintype "passive"))
      (node (ref "T1") (pin "12") (pinfunction "12_12") (pintype "passive"))
      (node (ref "T1") (pin "16") (pinfunction "16_16") (pintype "passive"))
    )
    (net (code "135") (name "Net-(D9-PadA)") (class "Default")
      (node (ref "D9") (pin "A") (pinfunction "A_A") (pintype "passive"))
      (node (ref "R7") (pin "1") (pinfunction "1_1") (pintype "passive"))
      (node (ref "T1") (pin "8") (pinfunction "8_8") (pintype "passive"))
    )
    (net (code "136") (name "Net-(E01A-I2)") (class "Default")
      (node (ref "E01") (pin "4") (pinfunction "I2_4") (pintype "input"))
      (node (ref "E01") (pin "5") (pinfunction "I3_5") (pintype "input"))
      (node (ref "E01") (pin "8") (pinfunction "O_8") (pintype "output"))
    )
    (net (code "137") (name "Net-(E03A-I0)") (class "Default")
      (node (ref "E03") (pin "1") (pinfunction "I0_1") (pintype "input"))
      (node (ref "E03") (pin "12") (pinfunction "I2_12") (pintype "input"))
      (node (ref "E03") (pin "13") (pinfunction "I3_13") (pintype "input"))
      (node (ref "E03") (pin "2") (pinfunction "I1_2") (pintype "input"))
      (node (ref "R12") (pin "1") (pinfunction "1_1") (pintype "passive"))
      (node (ref "U$2") (pin "AA1") (pinfunction "1_AA1") (pintype "bidirectional"))
    )
    (net (code "138") (name "Net-(E04A-O)") (class "Default")
      (node (ref "E04") (pin "3") (pinfunction "O_3") (pintype "output"))
      (node (ref "E36") (pin "8") (pinfunction "I0_8") (pintype "input"))
    )
    (net (code "139") (name "Net-(E07A-I2)") (class "Default")
      (node (ref "E07") (pin "4") (pinfunction "I2_4") (pintype "input"))
      (node (ref "E13") (pin "14") (pinfunction "O_14") (pintype "output"))
    )
    (net (code "140") (name "Net-(E07B-I0)") (class "Default")
      (node (ref "E07") (pin "10") (pinfunction "I1_10") (pintype "input"))
      (node (ref "E07") (pin "9") (pinfunction "I0_9") (pintype "input"))
      (node (ref "R11") (pin "1") (pinfunction "1_1") (pintype "passive"))
      (node (ref "U$2") (pin "AB1") (pinfunction "1_AB1") (pintype "bidirectional"))
    )
    (net (code "141") (name "Net-(E07B-I2)") (class "Default")
      (node (ref "E07") (pin "12") (pinfunction "I2_12") (pintype "input"))
      (node (ref "E07") (pin "13") (pinfunction "I3_13") (pintype "input"))
      (node (ref "R8") (pin "2") (pinfunction "2_2") (pintype "passive"))
    )
    (net (code "142") (name "Net-(E08A-I1)") (class "Default")
      (node (ref "E08") (pin "13") (pinfunction "I2_13") (pintype "input"))
      (node (ref "E08") (pin "2") (pinfunction "I1_2") (pintype "input"))
      (node (ref "E46") (pin "6") (pinfunction "O_6") (pintype "output"))
    )
    (net (code "143") (name "Net-(E08A-O)") (class "Default")
      (node (ref "E08") (pin "12") (pinfunction "O_12") (pintype "output"))
      (node (ref "E45") (pin "11") (pinfunction "CLK_11") (pintype "input"))
    )
    (net (code "144") (name "Net-(E08B-O)") (class "Default")
      (node (ref "E08") (pin "6") (pinfunction "O_6") (pintype "output"))
      (node (ref "E13") (pin "11") (pinfunction "I0_11") (pintype "input"))
      (node (ref "R30") (pin "1") (pinfunction "1_1") (pintype "passive"))
    )
    (net (code "145") (name "Net-(E08C-I0)") (class "Default")
      (node (ref "E08") (pin "10") (pinfunction "I1_10") (pintype "input"))
      (node (ref "E08") (pin "9") (pinfunction "I0_9") (pintype "input"))
      (node (ref "E09") (pin "5") (pinfunction "Q_5") (pintype "output"))
    )
    (net (code "146") (name "Net-(E08C-I2)") (class "Default")
      (node (ref "E08") (pin "11") (pinfunction "I2_11") (pintype "input"))
      (node (ref "E09") (pin "2") (pinfunction "D_2") (pintype "input"))
      (node (ref "E13") (pin "2") (pinfunction "O_2") (pintype "output"))
    )
    (net (code "147") (name "Net-(E08C-O)") (class "Default")
      (node (ref "E08") (pin "8") (pinfunction "O_8") (pintype "output"))
      (node (ref "E09") (pin "12") (pinfunction "D_12") (pintype "input"))
    )
    (net (code "148") (name "Net-(E10A-I1)") (class "Default")
      (node (ref "E10") (pin "2") (pinfunction "I1_2") (pintype "input"))
      (node (ref "E10") (pin "4") (pinfunction "I2_4") (pintype "input"))
      (node (ref "E10") (pin "5") (pinfunction "I3_5") (pintype "input"))
      (node (ref "E10") (pin "8") (pinfunction "O_8") (pintype "output"))
    )
    (net (code "149") (name "Net-(E11A-SR)") (class "Default")
      (node (ref "E11") (pin "2") (pinfunction "SR_2") (pintype "input"))
      (node (ref "E15") (pin "12") (pinfunction "QD_12") (pintype "output"))
    )
    (net (code "150") (name "Net-(E12A-O)") (class "Default")
      (node (ref "E12") (pin "8") (pinfunction "O_8") (pintype "output"))
      (node (ref "E22") (pin "8") (pinfunction "I0_8") (pintype "input"))
    )
    (net (code "151") (name "Net-(E13A-O)") (class "Default")
      (node (ref "E13") (pin "3") (pinfunction "O_3") (pintype "output"))
      (node (ref "E36") (pin "6") (pinfunction "I1_6") (pintype "input"))
    )
    (net (code "152") (name "Net-(E13D-O)") (class "Default")
      (node (ref "E13") (pin "13") (pinfunction "O_13") (pintype "output"))
      (node (ref "E45") (pin "13") (pinfunction "CLR_13") (pintype "input"))
    )
    (net (code "153") (name "Net-(E14A-O)") (class "Default")
      (node (ref "E14") (pin "10") (pinfunction "I1_10") (pintype "input"))
      (node (ref "E14") (pin "6") (pinfunction "O_6") (pintype "output"))
      (node (ref "E14") (pin "9") (pinfunction "I0_9") (pintype "input"))
    )
    (net (code "154") (name "Net-(E16A-I6)") (class "Default")
      (node (ref "E16") (pin "11") (pinfunction "I6_11") (pintype "input"))
      (node (ref "E16") (pin "12") (pinfunction "I7_12") (pintype "input"))
      (node (ref "E18") (pin "10") (pinfunction "O_10") (pintype "output"))
    )
    (net (code "155") (name "Net-(E16A-O)") (class "Default")
      (node (ref "E16") (pin "8") (pinfunction "O_8") (pintype "output"))
      (node (ref "E37") (pin "5") (pinfunction "I_5") (pintype "input"))
      (node (ref "E50") (pin "2") (pinfunction "D_2") (pintype "input"))
    )
    (net (code "156") (name "Net-(E17C-I0)") (class "Default")
      (node (ref "E17") (pin "12") (pinfunction "I1_12") (pintype "input"))
      (node (ref "E17") (pin "8") (pinfunction "I0_8") (pintype "input"))
      (node (ref "E36") (pin "5") (pinfunction "I0_5") (pintype "input"))
      (node (ref "E42") (pin "6") (pinfunction "O_6") (pintype "output"))
    )
    (net (code "157") (name "Net-(E18D-O)") (class "Default")
      (node (ref "E18") (pin "8") (pinfunction "O_8") (pintype "output"))
      (node (ref "E41") (pin "11") (pinfunction "I0_11") (pintype "input"))
    )
    (net (code "158") (name "Net-(E19A-I2)") (class "Default")
      (node (ref "E19") (pin "4") (pinfunction "I2_4") (pintype "input"))
      (node (ref "E19") (pin "5") (pinfunction "I3_5") (pintype "input"))
      (node (ref "E19") (pin "8") (pinfunction "O_8") (pintype "output"))
    )
    (net (code "159") (name "Net-(E21A-Q)") (class "Default")
      (node (ref "E21") (pin "12") (pinfunction "D_12") (pintype "input"))
      (node (ref "E21") (pin "5") (pinfunction "Q_5") (pintype "output"))
    )
    (net (code "160") (name "Net-(E22A-I1)") (class "Default")
      (node (ref "E22") (pin "3") (pinfunction "I1_3") (pintype "input"))
      (node (ref "E22") (pin "4") (pinfunction "O_4") (pintype "output"))
    )
    (net (code "161") (name "Net-(E22A-O)") (class "Default")
      (node (ref "E22") (pin "1") (pinfunction "O_1") (pintype "output"))
      (node (ref "E31") (pin "2") (pinfunction "D_2") (pintype "input"))
    )
    (net (code "162") (name "Net-(E22B-I1)") (class "Default")
      (node (ref "E22") (pin "10") (pinfunction "O_10") (pintype "output"))
      (node (ref "E22") (pin "6") (pinfunction "I1_6") (pintype "input"))
    )
    (net (code "163") (name "Net-(E23A-I1)") (class "Default")
      (node (ref "E23") (pin "2") (pinfunction "I1_2") (pintype "input"))
      (node (ref "E48") (pin "12") (pinfunction "O_12") (pintype "output"))
    )
    (net (code "164") (name "Net-(E23B-O)") (class "Default")
      (node (ref "E23") (pin "6") (pinfunction "O_6") (pintype "output"))
      (node (ref "E49") (pin "10") (pinfunction "PRE_10") (pintype "input"))
    )
    (net (code "165") (name "Net-(E23C-I1)") (class "Default")
      (node (ref "E23") (pin "10") (pinfunction "I1_10") (pintype "input"))
      (node (ref "E37") (pin "2") (pinfunction "O_2") (pintype "open_collector"))
      (node (ref "E37") (pin "4") (pinfunction "O_4") (pintype "open_collector"))
      (node (ref "R37") (pin "1") (pinfunction "1_1") (pintype "passive"))
    )
    (net (code "166") (name "Net-(E23D-I1)") (class "Default")
      (node (ref "E23") (pin "13") (pinfunction "I1_13") (pintype "input"))
      (node (ref "E32") (pin "12") (pinfunction "~{Q}_12") (pintype "output"))
    )
    (net (code "167") (name "Net-(E23D-O)") (class "Default")
      (node (ref "E23") (pin "11") (pinfunction "O_11") (pintype "output"))
      (node (ref "R31") (pin "1") (pinfunction "1_1") (pintype "passive"))
      (node (ref "R32") (pin "1") (pinfunction "1_1") (pintype "passive"))
    )
    (net (code "168") (name "Net-(E24B-I0)") (class "Default")
      (node (ref "E24") (pin "10") (pinfunction "I1_10") (pintype "input"))
      (node (ref "E24") (pin "12") (pinfunction "I2_12") (pintype "input"))
      (node (ref "E24") (pin "13") (pinfunction "I3_13") (pintype "input"))
      (node (ref "E24") (pin "9") (pinfunction "I0_9") (pintype "input"))
      (node (ref "E26") (pin "8") (pinfunction "~{Q}_8") (pintype "output"))
    )
    (net (code "169") (name "Net-(E25A-S1)") (class "Default")
      (node (ref "E25") (pin "10") (pinfunction "S1_10") (pintype "input"))
      (node (ref "E30") (pin "8") (pinfunction "~{Q}_8") (pintype "output"))
    )
    (net (code "170") (name "Net-(E27A-I0)") (class "Default")
      (node (ref "C39") (pin "2") (pinfunction "2_2") (pintype "passive"))
      (node (ref "C40") (pin "2") (pinfunction "2_2") (pintype "passive"))
      (node (ref "D11") (pin "C") (pinfunction "C_C") (pintype "passive"))
      (node (ref "D12") (pin "A") (pinfunction "A_A") (pintype "passive"))
      (node (ref "E27") (pin "4") (pinfunction "I0_4") (pintype "input"))
      (node (ref "E27") (pin "5") (pinfunction "I1_5") (pintype "input"))
      (node (ref "R2") (pin "2") (pinfunction "2_2") (pintype "passive"))
    )
    (net (code "171") (name "Net-(E27A-O)") (class "Default")
      (node (ref "C39") (pin "1") (pinfunction "1_1") (pintype "passive"))
      (node (ref "C40") (pin "1") (pinfunction "1_1") (pintype "passive"))
      (node (ref "E27") (pin "3") (pinfunction "O_3") (pintype "output"))
      (node (ref "E43") (pin "10") (pinfunction "I1_10") (pintype "input"))
      (node (ref "E43") (pin "12") (pinfunction "I2_12") (pintype "input"))
      (node (ref "E43") (pin "13") (pinfunction "I3_13") (pintype "input"))
      (node (ref "E43") (pin "9") (pinfunction "I0_9") (pintype "input"))
    )
    (net (code "172") (name "Net-(E30A-Q)") (class "Default")
      (node (ref "E30") (pin "5") (pinfunction "Q_5") (pintype "output"))
      (node (ref "E35") (pin "11") (pinfunction "I_11") (pintype "input"))
    )
    (net (code "173") (name "Net-(E30B-PRE)") (class "Default")
      (node (ref "E30") (pin "10") (pinfunction "PRE_10") (pintype "input"))
      (node (ref "R15") (pin "1") (pinfunction "1_1") (pintype "passive"))
      (node (ref "W1") (pin "2") (pinfunction "2_2") (pintype "passive"))
    )
    (net (code "174") (name "Net-(E31B-CLK)") (class "Default")
      (node (ref "E31") (pin "11") (pinfunction "CLK_11") (pintype "input"))
      (node (ref "E32") (pin "4") (pinfunction "~{Q}_4") (pintype "output"))
    )
    (net (code "175") (name "Net-(E32A-C)") (class "Default")
      (node (ref "C35") (pin "+") (pinfunction "+_+") (pintype "passive"))
      (node (ref "E32") (pin "14") (pinfunction "C_14") (pintype "input"))
    )
    (net (code "176") (name "Net-(E32A-R{slash}C)") (class "Default")
      (node (ref "C35") (pin "-") (pinfunction "-_-") (pintype "passive"))
      (node (ref "E32") (pin "15") (pinfunction "R/C_15") (pintype "input"))
      (node (ref "R27") (pin "1") (pinfunction "1_1") (pintype "passive"))
    )
    (net (code "177") (name "Net-(E32B-C)") (class "Default")
      (node (ref "C48") (pin "1") (pinfunction "1_1") (pintype "passive"))
      (node (ref "E32") (pin "6") (pinfunction "C_6") (pintype "input"))
    )
    (net (code "178") (name "Net-(E32B-R{slash}C)") (class "Default")
      (node (ref "C48") (pin "2") (pinfunction "2_2") (pintype "passive"))
      (node (ref "E32") (pin "7") (pinfunction "R/C_7") (pintype "input"))
      (node (ref "R26") (pin "1") (pinfunction "1_1") (pintype "passive"))
    )
    (net (code "179") (name "Net-(E36D-O)") (class "Default")
      (node (ref "E36") (pin "13") (pinfunction "O_13") (pintype "open_collector"))
      (node (ref "R1") (pin "1") (pinfunction "1_1") (pintype "passive"))
      (node (ref "R2") (pin "1") (pinfunction "1_1") (pintype "passive"))
    )
    (net (code "180") (name "Net-(E37D-I)") (class "Default")
      (node (ref "E37") (pin "9") (pinfunction "I_9") (pintype "input"))
      (node (ref "E49") (pin "6") (pinfunction "~{Q}_6") (pintype "output"))
    )
    (net (code "181") (name "Net-(E38A-I0)") (class "Default")
      (node (ref "E38") (pin "1") (pinfunction "I0_1") (pintype "input"))
      (node (ref "E47") (pin "11") (pinfunction "O_11") (pintype "output"))
    )
    (net (code "182") (name "Net-(E38B-I2)") (class "Default")
      (node (ref "E38") (pin "12") (pinfunction "I2_12") (pintype "input"))
      (node (ref "E47") (pin "3") (pinfunction "O_3") (pintype "output"))
    )
    (net (code "183") (name "Net-(E40B-~{Q})") (class "Default")
      (node (ref "E40") (pin "8") (pinfunction "~{Q}_8") (pintype "output"))
      (node (ref "E44") (pin "10") (pinfunction "S1_10") (pintype "input"))
    )
    (net (code "184") (name "Net-(E41A-I0)") (class "Default")
      (node (ref "E41") (pin "2") (pinfunction "I0_2") (pintype "input"))
      (node (ref "E42") (pin "4") (pinfunction "O_4") (pintype "output"))
    )
    (net (code "185") (name "Net-(E41B-I0)") (class "Default")
      (node (ref "E41") (pin "5") (pinfunction "I0_5") (pintype "input"))
      (node (ref "E42") (pin "2") (pinfunction "O_2") (pintype "output"))
    )
    (net (code "186") (name "Net-(E42E-O)") (class "Default")
      (node (ref "E42") (pin "10") (pinfunction "O_10") (pintype "output"))
      (node (ref "E48") (pin "3") (pinfunction "I0_3") (pintype "input"))
    )
    (net (code "187") (name "Net-(E43A-I3)") (class "Default")
      (node (ref "E43") (pin "5") (pinfunction "I3_5") (pintype "input"))
      (node (ref "E47") (pin "8") (pinfunction "O_8") (pintype "output"))
    )
    (net (code "188") (name "Net-(E48B-O)") (class "Default")
      (node (ref "E48") (pin "6") (pinfunction "O_6") (pintype "output"))
      (node (ref "E49") (pin "2") (pinfunction "D_2") (pintype "input"))
    )
    (net (code "189") (name "Net-(Q1-B)") (class "Default")
      (node (ref "Q1") (pin "2") (pinfunction "B_2") (pintype "passive"))
      (node (ref "R31") (pin "2") (pinfunction "2_2") (pintype "passive"))
    )
    (net (code "190") (name "Net-(Q1-C)") (class "Default")
      (node (ref "Q1") (pin "3") (pinfunction "C_3") (pintype "passive"))
      (node (ref "R33") (pin "1") (pinfunction "1_1") (pintype "passive"))
    )
    (net (code "191") (name "Net-(Q2-B)") (class "Default")
      (node (ref "C43") (pin "1") (pinfunction "1_1") (pintype "passive"))
      (node (ref "C45") (pin "1") (pinfunction "1_1") (pintype "passive"))
      (node (ref "Q2") (pin "2") (pinfunction "B_2") (pintype "passive"))
      (node (ref "R5") (pin "1") (pinfunction "1_1") (pintype "passive"))
    )
    (net (code "192") (name "Net-(Q2-E)") (class "Default")
      (node (ref "C46") (pin "1") (pinfunction "1_1") (pintype "passive"))
      (node (ref "Q2") (pin "1") (pinfunction "E_1") (pintype "passive"))
      (node (ref "R6") (pin "1") (pinfunction "1_1") (pintype "passive"))
    )
    (net (code "193") (name "Net-(R8-Pad1)") (class "Default")
      (node (ref "R8") (pin "1") (pinfunction "1_1") (pintype "passive"))
      (node (ref "T1") (pin "1") (pinfunction "1_1") (pintype "passive"))
    )
    (net (code "194") (name "Net-(T1-Pad2)") (class "Default")
      (node (ref "T1") (pin "2") (pinfunction "2_2") (pintype "passive"))
      (node (ref "T1") (pin "3") (pinfunction "3_3") (pintype "passive"))
    )
    (net (code "195") (name "Net-(T1-Pad4)") (class "Default")
      (node (ref "T1") (pin "4") (pinfunction "4_4") (pintype "passive"))
      (node (ref "T1") (pin "5") (pinfunction "5_5") (pintype "passive"))
    )
    (net (code "196") (name "Net-(T1-Pad6)") (class "Default")
      (node (ref "T1") (pin "6") (pinfunction "6_6") (pintype "passive"))
      (node (ref "T1") (pin "7") (pinfunction "7_7") (pintype "passive"))
    )
    (net (code "197") (name "Net-(T1-Pad10)") (class "Default")
      (node (ref "T1") (pin "10") (pinfunction "10_10") (pintype "passive"))
      (node (ref "T1") (pin "11") (pinfunction "11_11") (pintype "passive"))
    )
    (net (code "198") (name "Net-(T1-Pad14)") (class "Default")
      (node (ref "T1") (pin "14") (pinfunction "14_14") (pintype "passive"))
      (node (ref "T1") (pin "15") (pinfunction "15_15") (pintype "passive"))
    )
    (net (code "199") (name "VCC") (class "Default")
      (node (ref "C1") (pin "1") (pinfunction "1_1") (pintype "passive"))
      (node (ref "C10") (pin "1") (pinfunction "1_1") (pintype "passive"))
      (node (ref "C11") (pin "1") (pinfunction "1_1") (pintype "passive"))
      (node (ref "C12") (pin "1") (pinfunction "1_1") (pintype "passive"))
      (node (ref "C13") (pin "1") (pinfunction "1_1") (pintype "passive"))
      (node (ref "C14") (pin "1") (pinfunction "1_1") (pintype "passive"))
      (node (ref "C15") (pin "1") (pinfunction "1_1") (pintype "passive"))
      (node (ref "C16") (pin "1") (pinfunction "1_1") (pintype "passive"))
      (node (ref "C17") (pin "1") (pinfunction "1_1") (pintype "passive"))
      (node (ref "C18") (pin "1") (pinfunction "1_1") (pintype "passive"))
      (node (ref "C19") (pin "1") (pinfunction "1_1") (pintype "passive"))
      (node (ref "C2") (pin "1") (pinfunction "1_1") (pintype "passive"))
      (node (ref "C20") (pin "1") (pinfunction "1_1") (pintype "passive"))
      (node (ref "C21") (pin "1") (pinfunction "1_1") (pintype "passive"))
      (node (ref "C22") (pin "1") (pinfunction "1_1") (pintype "passive"))
      (node (ref "C23") (pin "1") (pinfunction "1_1") (pintype "passive"))
      (node (ref "C24") (pin "1") (pinfunction "1_1") (pintype "passive"))
      (node (ref "C25") (pin "1") (pinfunction "1_1") (pintype "passive"))
      (node (ref "C26") (pin "1") (pinfunction "1_1") (pintype "passive"))
      (node (ref "C27") (pin "1") (pinfunction "1_1") (pintype "passive"))
      (node (ref "C28") (pin "1") (pinfunction "1_1") (pintype "passive"))
      (node (ref "C29") (pin "1") (pinfunction "1_1") (pintype "passive"))
      (node (ref "C3") (pin "1") (pinfunction "1_1") (pintype "passive"))
      (node (ref "C30") (pin "1") (pinfunction "1_1") (pintype "passive"))
      (node (ref "C31") (pin "1") (pinfunction "1_1") (pintype "passive"))
      (node (ref "C32") (pin "1") (pinfunction "1_1") (pintype "passive"))
      (node (ref "C33") (pin "1") (pinfunction "1_1") (pintype "passive"))
      (node (ref "C34") (pin "1") (pinfunction "1_1") (pintype "passive"))
      (node (ref "C36") (pin "+") (pinfunction "+_+") (pintype "passive"))
      (node (ref "C37") (pin "+") (pinfunction "+_+") (pintype "passive"))
      (node (ref "C38") (pin "+") (pinfunction "+_+") (pintype "passive"))
      (node (ref "C4") (pin "1") (pinfunction "1_1") (pintype "passive"))
      (node (ref "C41") (pin "1") (pinfunction "1_1") (pintype "passive"))
      (node (ref "C5") (pin "1") (pinfunction "1_1") (pintype "passive"))
      (node (ref "C6") (pin "1") (pinfunction "1_1") (pintype "passive"))
      (node (ref "C7") (pin "1") (pinfunction "1_1") (pintype "passive"))
      (node (ref "C8") (pin "1") (pinfunction "1_1") (pintype "passive"))
      (node (ref "C9") (pin "1") (pinfunction "1_1") (pintype "passive"))
      (node (ref "D12") (pin "C") (pinfunction "C_C") (pintype "passive"))
      (node (ref "Q2") (pin "3") (pinfunction "C_3") (pintype "passive"))
      (node (ref "R1") (pin "2") (pinfunction "2_2") (pintype "passive"))
      (node (ref "R10") (pin "2") (pinfunction "2_2") (pintype "passive"))
      (node (ref "R11") (pin "2") (pinfunction "2_2") (pintype "passive"))
      (node (ref "R12") (pin "2") (pinfunction "2_2") (pintype "passive"))
      (node (ref "R13") (pin "2") (pinfunction "2_2") (pintype "passive"))
      (node (ref "R14") (pin "2") (pinfunction "2_2") (pintype "passive"))
      (node (ref "R15") (pin "2") (pinfunction "2_2") (pintype "passive"))
      (node (ref "R16") (pin "2") (pinfunction "2_2") (pintype "passive"))
      (node (ref "R17") (pin "2") (pinfunction "2_2") (pintype "passive"))
      (node (ref "R18") (pin "2") (pinfunction "2_2") (pintype "passive"))
      (node (ref "R19") (pin "2") (pinfunction "2_2") (pintype "passive"))
      (node (ref "R20") (pin "2") (pinfunction "2_2") (pintype "passive"))
      (node (ref "R22") (pin "1") (pinfunction "1_1") (pintype "passive"))
      (node (ref "R23") (pin "2") (pinfunction "2_2") (pintype "passive"))
      (node (ref "R24") (pin "2") (pinfunction "2_2") (pintype "passive"))
      (node (ref "R26") (pin "2") (pinfunction "2_2") (pintype "passive"))
      (node (ref "R27") (pin "2") (pinfunction "2_2") (pintype "passive"))
      (node (ref "R28") (pin "2") (pinfunction "2_2") (pintype "passive"))
      (node (ref "R29") (pin "2") (pinfunction "2_2") (pintype "passive"))
      (node (ref "R3") (pin "2") (pinfunction "2_2") (pintype "passive"))
      (node (ref "R30") (pin "2") (pinfunction "2_2") (pintype "passive"))
      (node (ref "R32") (pin "2") (pinfunction "2_2") (pintype "passive"))
      (node (ref "R33") (pin "2") (pinfunction "2_2") (pintype "passive"))
      (node (ref "R35") (pin "2") (pinfunction "2_2") (pintype "passive"))
      (node (ref "R36") (pin "2") (pinfunction "2_2") (pintype "passive"))
      (node (ref "R37") (pin "2") (pinfunction "2_2") (pintype "passive"))
      (node (ref "R38") (pin "2") (pinfunction "2_2") (pintype "passive"))
      (node (ref "R39") (pin "2") (pinfunction "2_2") (pintype "passive"))
      (node (ref "R4") (pin "2") (pinfunction "2_2") (pintype "passive"))
      (node (ref "R5") (pin "2") (pinfunction "2_2") (pintype "passive"))
      (node (ref "R7") (pin "2") (pinfunction "2_2") (pintype "passive"))
      (node (ref "R9") (pin "2") (pinfunction "2_2") (pintype "passive"))
      (node (ref "U$2") (pin "AA2") (pinfunction "1_AA2") (pintype "bidirectional"))
      (node (ref "U$2") (pin "BA2") (pinfunction "1_BA2") (pintype "bidirectional"))
      (node (ref "U$2") (pin "CA2") (pinfunction "1_CA2") (pintype "bidirectional"))
      (node (ref "Y1B") (pin "14") (pinfunction "VCC_14") (pintype "power_in"))
    )
    (net (code "200") (name "unconnected-(E02A-QA-Pad15)") (class "Default")
      (node (ref "E02") (pin "15") (pinfunction "QA_15") (pintype "output"))
    )
    (net (code "201") (name "unconnected-(E06A-QA-Pad15)") (class "Default")
      (node (ref "E06") (pin "15") (pinfunction "QA_15") (pintype "output"))
    )
    (net (code "202") (name "unconnected-(E06A-QC-Pad13)") (class "Default")
      (node (ref "E06") (pin "13") (pinfunction "QC_13") (pintype "output"))
    )
    (net (code "203") (name "unconnected-(E09A-~{Q}-Pad6)") (class "Default")
      (node (ref "E09") (pin "6") (pinfunction "~{Q}_6") (pintype "output"))
    )
    (net (code "204") (name "unconnected-(E09B-Q-Pad9)") (class "Default")
      (node (ref "E09") (pin "9") (pinfunction "Q_9") (pintype "output"))
    )
    (net (code "205") (name "unconnected-(E11A-QA-Pad15)") (class "Default")
      (node (ref "E11") (pin "15") (pinfunction "QA_15") (pintype "output"))
    )
    (net (code "206") (name "unconnected-(E11A-QD-Pad12)") (class "Default")
      (node (ref "E11") (pin "12") (pinfunction "QD_12") (pintype "output"))
    )
    (net (code "207") (name "unconnected-(E15A-QB-Pad14)") (class "Default")
      (node (ref "E15") (pin "14") (pinfunction "QB_14") (pintype "output"))
    )
    (net (code "208") (name "unconnected-(E15A-QC-Pad13)") (class "Default")
      (node (ref "E15") (pin "13") (pinfunction "QC_13") (pintype "output"))
    )
    (net (code "209") (name "unconnected-(E20A-QB-Pad14)") (class "Default")
      (node (ref "E20") (pin "14") (pinfunction "QB_14") (pintype "output"))
    )
    (net (code "210") (name "unconnected-(E21B-Q-Pad9)") (class "Default")
      (node (ref "E21") (pin "9") (pinfunction "Q_9") (pintype "output"))
    )
    (net (code "211") (name "unconnected-(E26A-~{Q}-Pad6)") (class "Default")
      (node (ref "E26") (pin "6") (pinfunction "~{Q}_6") (pintype "output"))
    )
    (net (code "212") (name "unconnected-(E26B-Q-Pad9)") (class "Default")
      (node (ref "E26") (pin "9") (pinfunction "Q_9") (pintype "output"))
    )
    (net (code "213") (name "unconnected-(E29A-QA-Pad15)") (class "Default")
      (node (ref "E29") (pin "15") (pinfunction "QA_15") (pintype "output"))
    )
    (net (code "214") (name "unconnected-(E29A-QB-Pad14)") (class "Default")
      (node (ref "E29") (pin "14") (pinfunction "QB_14") (pintype "output"))
    )
    (net (code "215") (name "unconnected-(E29A-QC-Pad13)") (class "Default")
      (node (ref "E29") (pin "13") (pinfunction "QC_13") (pintype "output"))
    )
    (net (code "216") (name "unconnected-(E30A-~{Q}-Pad6)") (class "Default")
      (node (ref "E30") (pin "6") (pinfunction "~{Q}_6") (pintype "output"))
    )
    (net (code "217") (name "unconnected-(E30B-Q-Pad9)") (class "Default")
      (node (ref "E30") (pin "9") (pinfunction "Q_9") (pintype "output"))
    )
    (net (code "218") (name "unconnected-(E31A-~{Q}-Pad6)") (class "Default")
      (node (ref "E31") (pin "6") (pinfunction "~{Q}_6") (pintype "output"))
    )
    (net (code "219") (name "unconnected-(E31B-Q-Pad9)") (class "Default")
      (node (ref "E31") (pin "9") (pinfunction "Q_9") (pintype "output"))
    )
    (net (code "220") (name "unconnected-(E32A-Q-Pad13)") (class "Default")
      (node (ref "E32") (pin "13") (pinfunction "Q_13") (pintype "output"))
    )
    (net (code "221") (name "unconnected-(E32B-Q-Pad5)") (class "Default")
      (node (ref "E32") (pin "5") (pinfunction "Q_5") (pintype "output"))
    )
    (net (code "222") (name "unconnected-(E34A-QA-Pad15)") (class "Default")
      (node (ref "E34") (pin "15") (pinfunction "QA_15") (pintype "output"))
    )
    (net (code "223") (name "unconnected-(E39A-QA-Pad15)") (class "Default")
      (node (ref "E39") (pin "15") (pinfunction "QA_15") (pintype "output"))
    )
    (net (code "224") (name "unconnected-(E40A-~{Q}-Pad6)") (class "Default")
      (node (ref "E40") (pin "6") (pinfunction "~{Q}_6") (pintype "output"))
    )
    (net (code "225") (name "unconnected-(E40B-Q-Pad9)") (class "Default")
      (node (ref "E40") (pin "9") (pinfunction "Q_9") (pintype "output"))
    )
    (net (code "226") (name "unconnected-(E44A-QA-Pad15)") (class "Default")
      (node (ref "E44") (pin "15") (pinfunction "QA_15") (pintype "output"))
    )
    (net (code "227") (name "unconnected-(E44A-QB-Pad14)") (class "Default")
      (node (ref "E44") (pin "14") (pinfunction "QB_14") (pintype "output"))
    )
    (net (code "228") (name "unconnected-(E44A-QC-Pad13)") (class "Default")
      (node (ref "E44") (pin "13") (pinfunction "QC_13") (pintype "output"))
    )
    (net (code "229") (name "unconnected-(E45B-~{Q}-Pad8)") (class "Default")
      (node (ref "E45") (pin "8") (pinfunction "~{Q}_8") (pintype "output"))
    )
    (net (code "230") (name "unconnected-(E49A-Q-Pad5)") (class "Default")
      (node (ref "E49") (pin "5") (pinfunction "Q_5") (pintype "output"))
    )
    (net (code "231") (name "unconnected-(E49B-~{Q}-Pad8)") (class "Default")
      (node (ref "E49") (pin "8") (pinfunction "~{Q}_8") (pintype "output"))
    )
    (net (code "232") (name "unconnected-(E50A-8-Pad6)") (class "Default")
      (node (ref "E50") (pin "6") (pinfunction "8_6") (pintype "output"))
    )
    (net (code "233") (name "unconnected-(E50A-9-Pad7)") (class "Default")
      (node (ref "E50") (pin "7") (pinfunction "9_7") (pintype "output"))
    )
    (net (code "234") (name "unconnected-(Y1B-OUT-Pad8)") (class "Default")
      (node (ref "Y1B") (pin "8") (pinfunction "OUT_8") (pintype "output"))
    )
  )
)
